# permamote.net
KiCad netlist of a schematic drawn in EAGLE
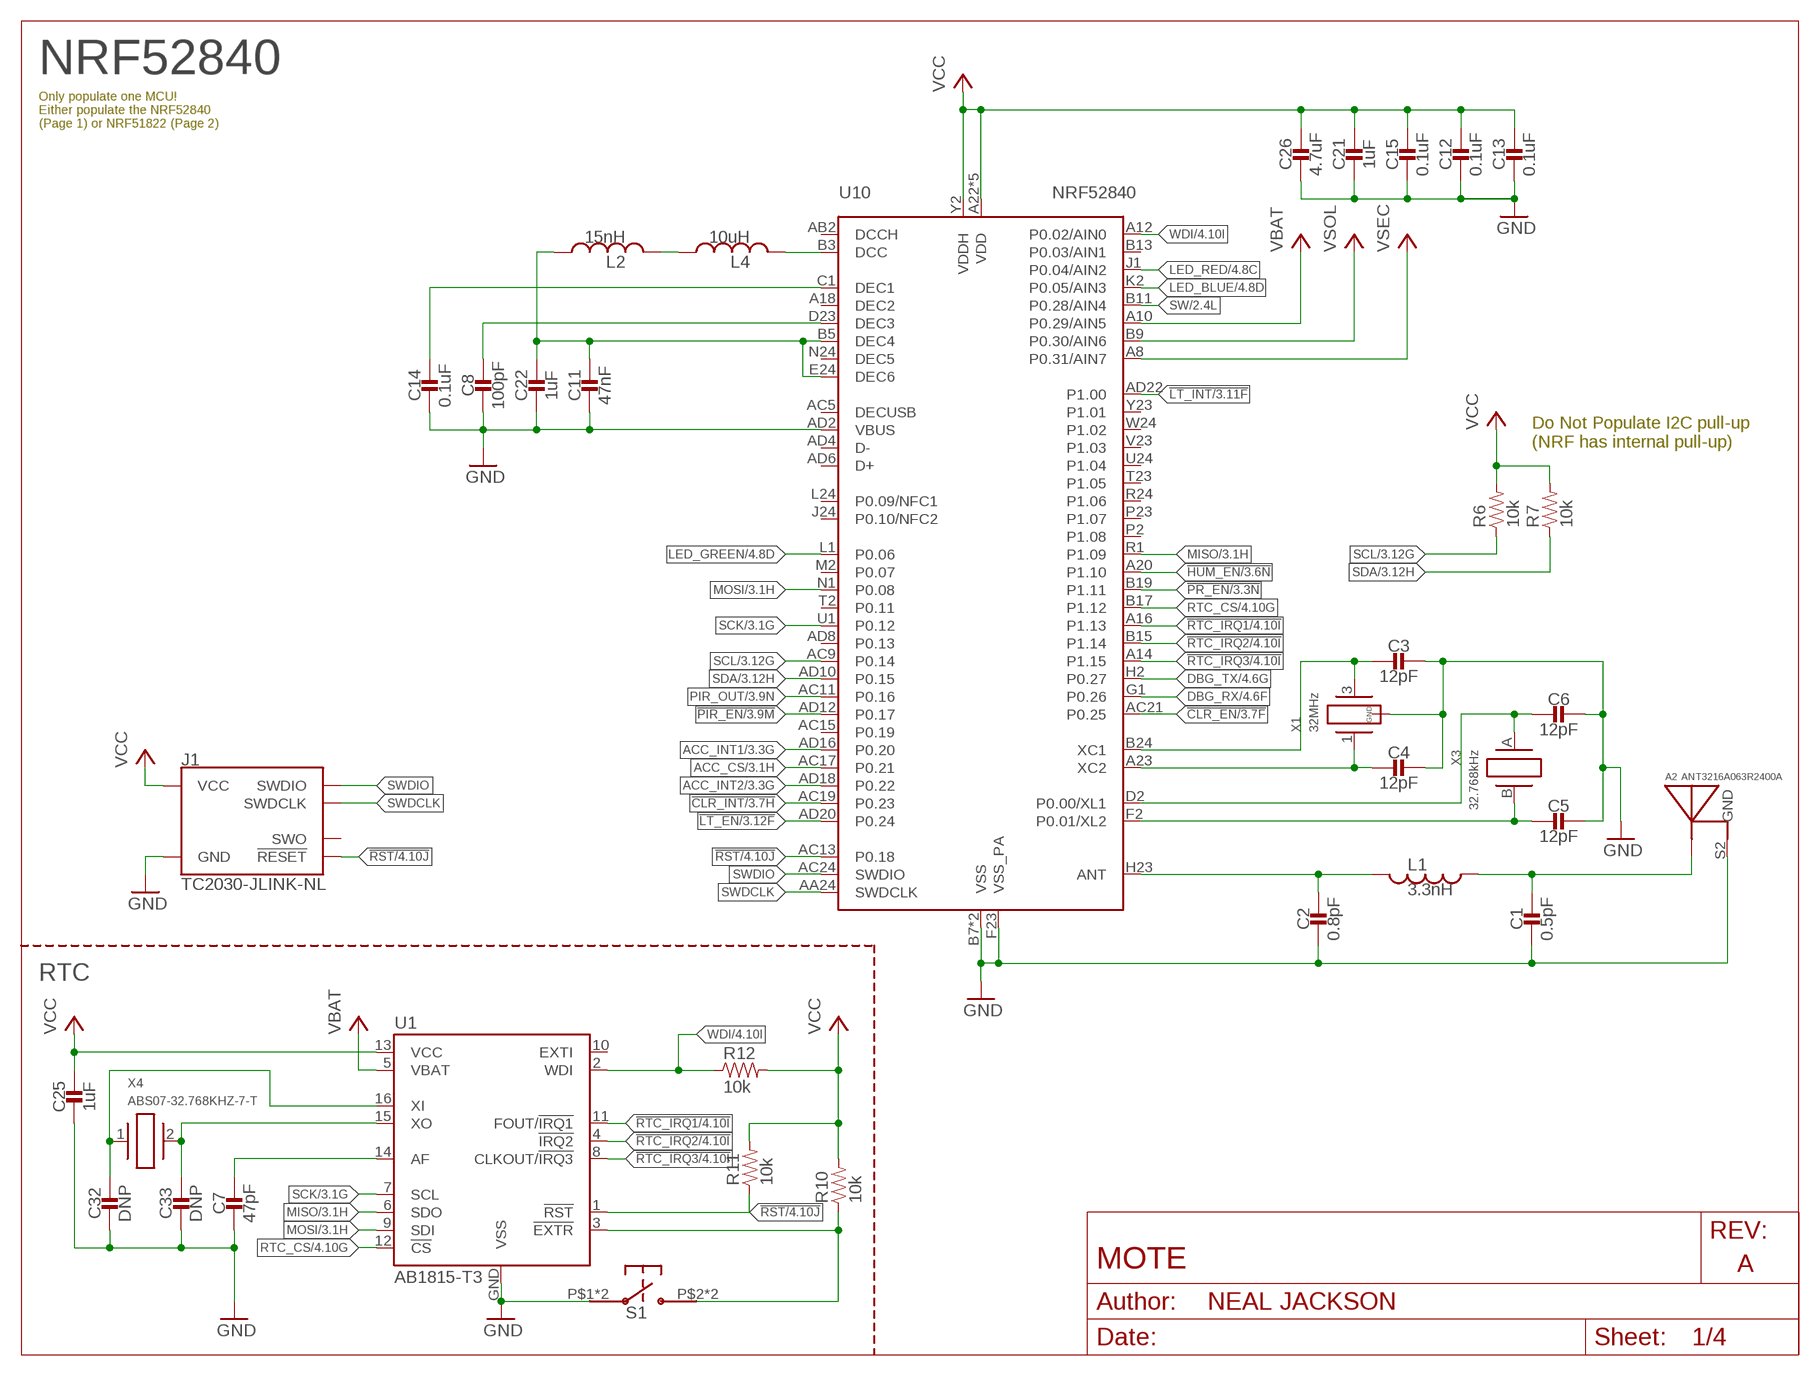
[diagram p0: schematic, sheet 1]
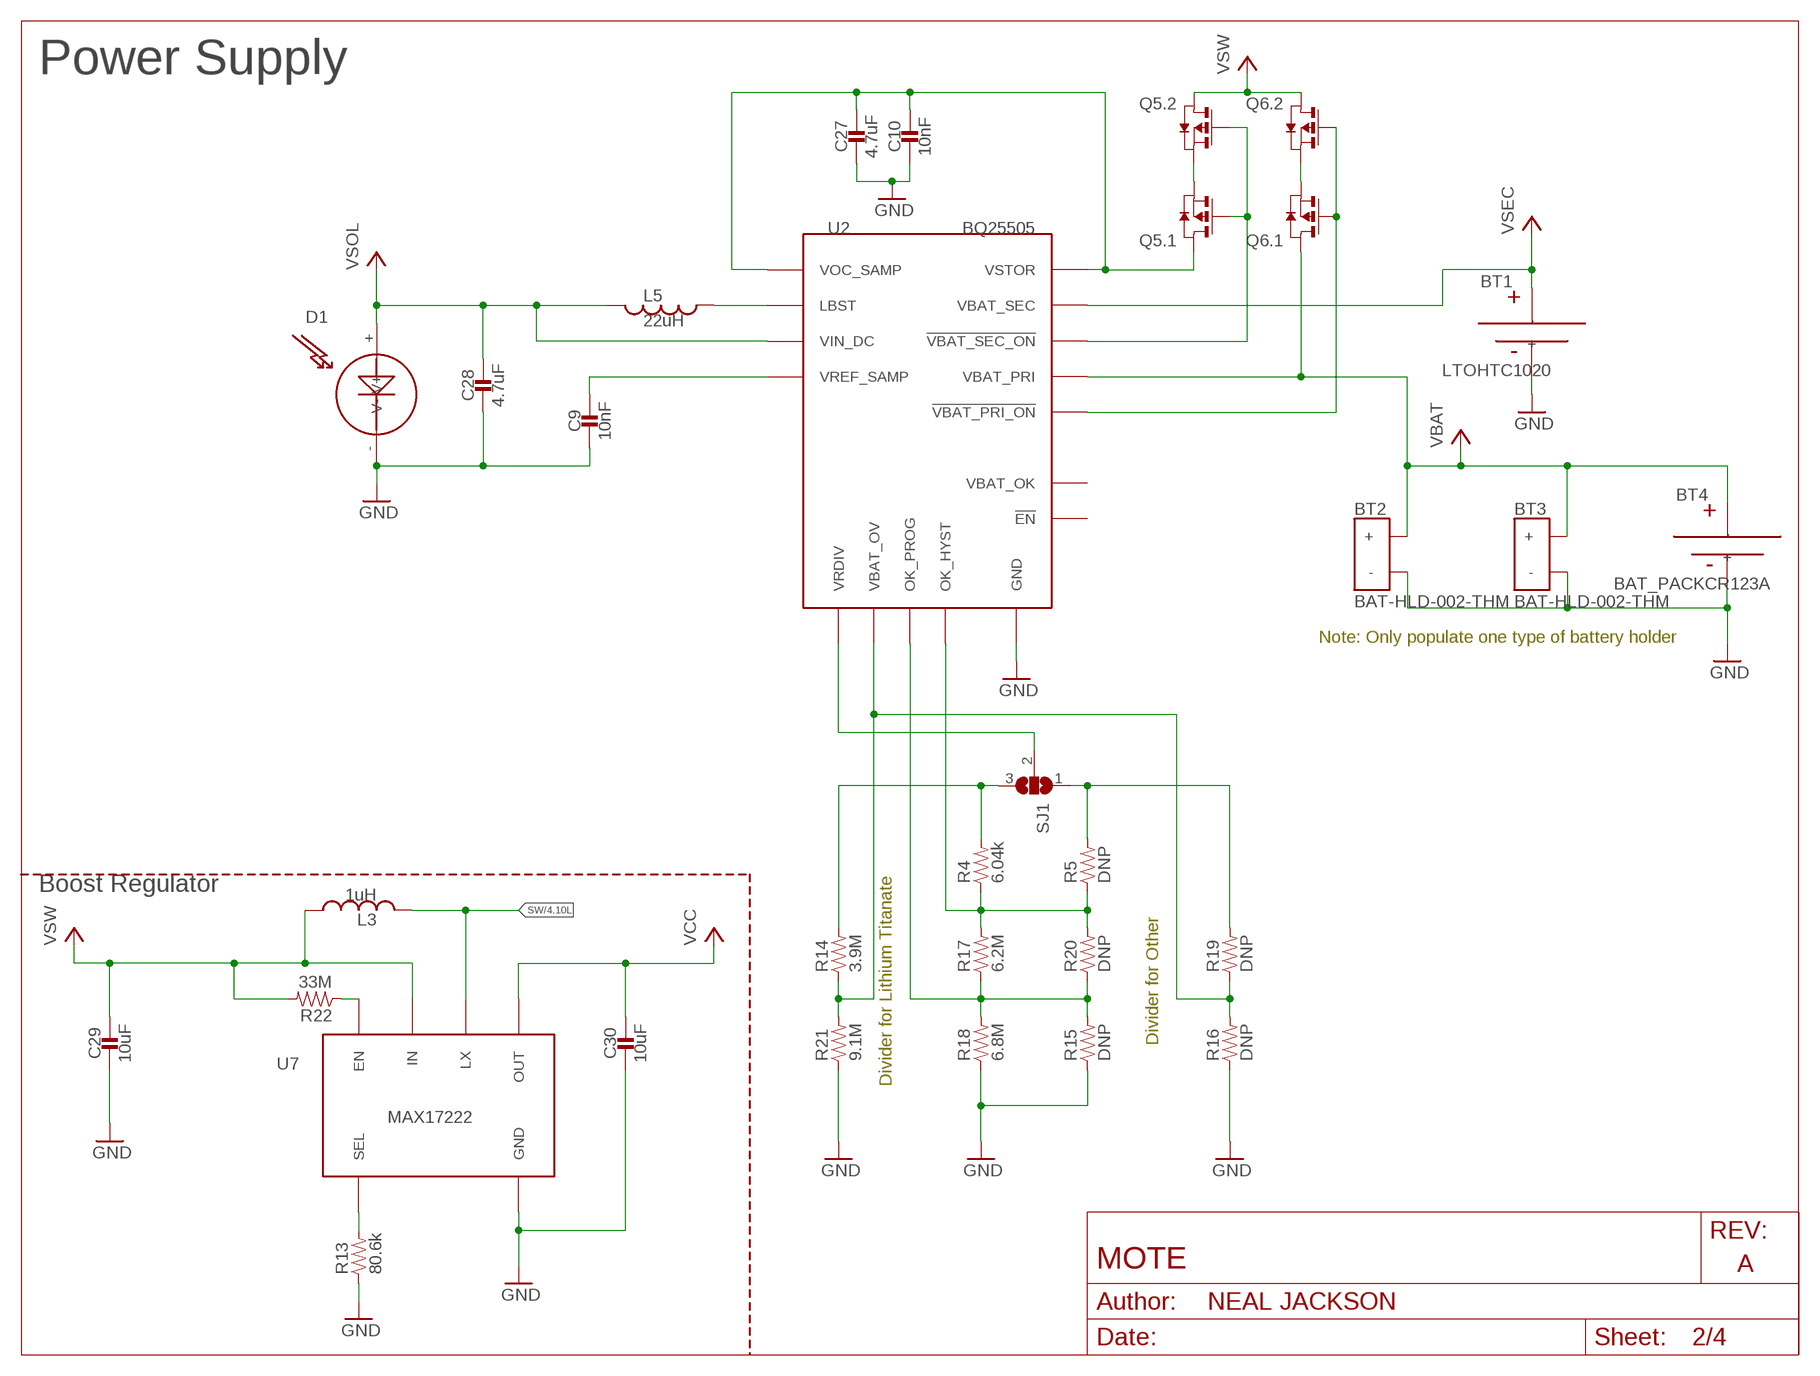
[diagram p1: schematic, sheet 2]
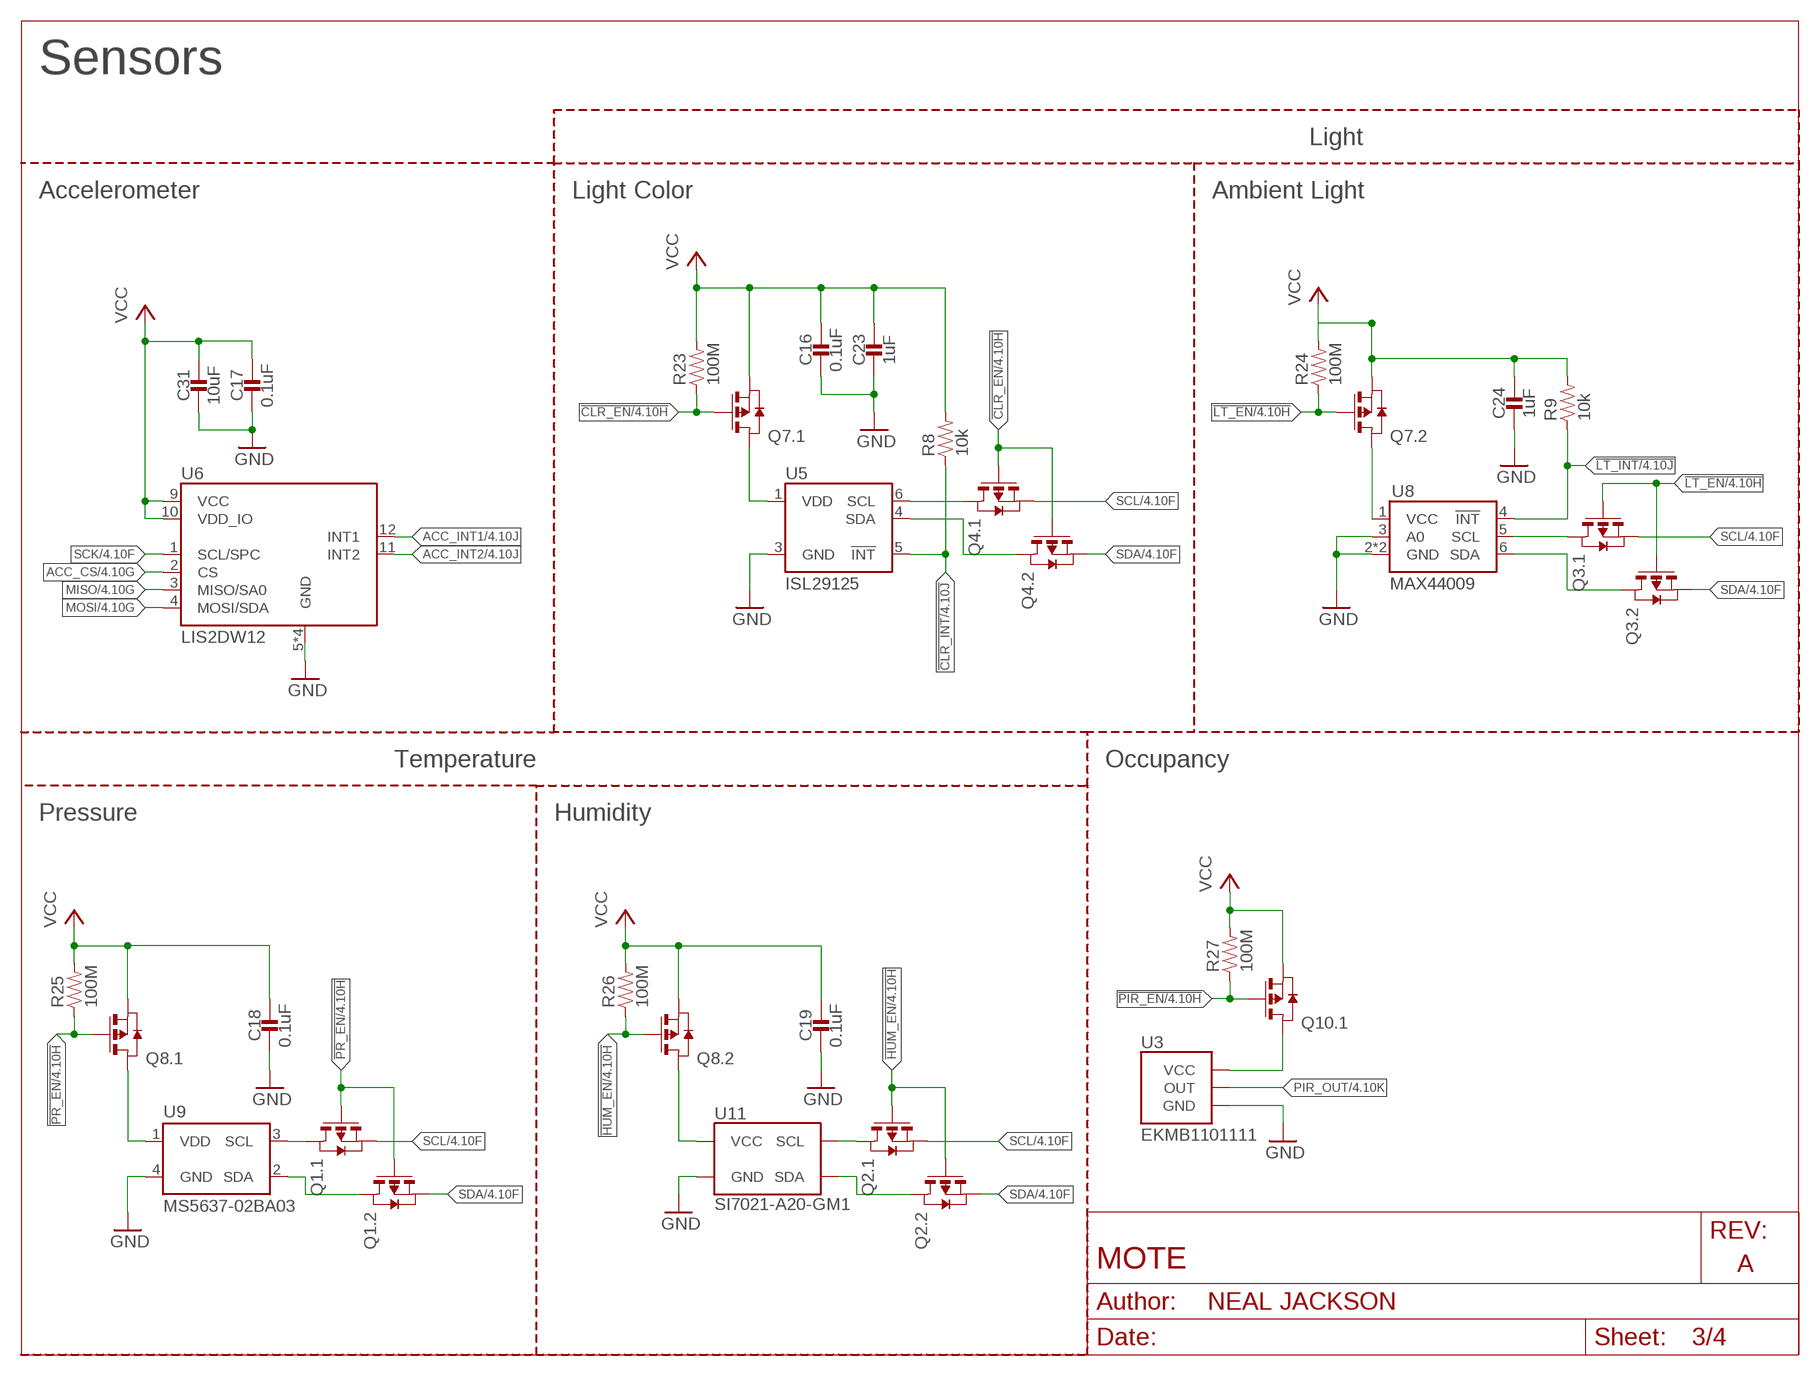
[diagram p2: schematic, sheet 3]
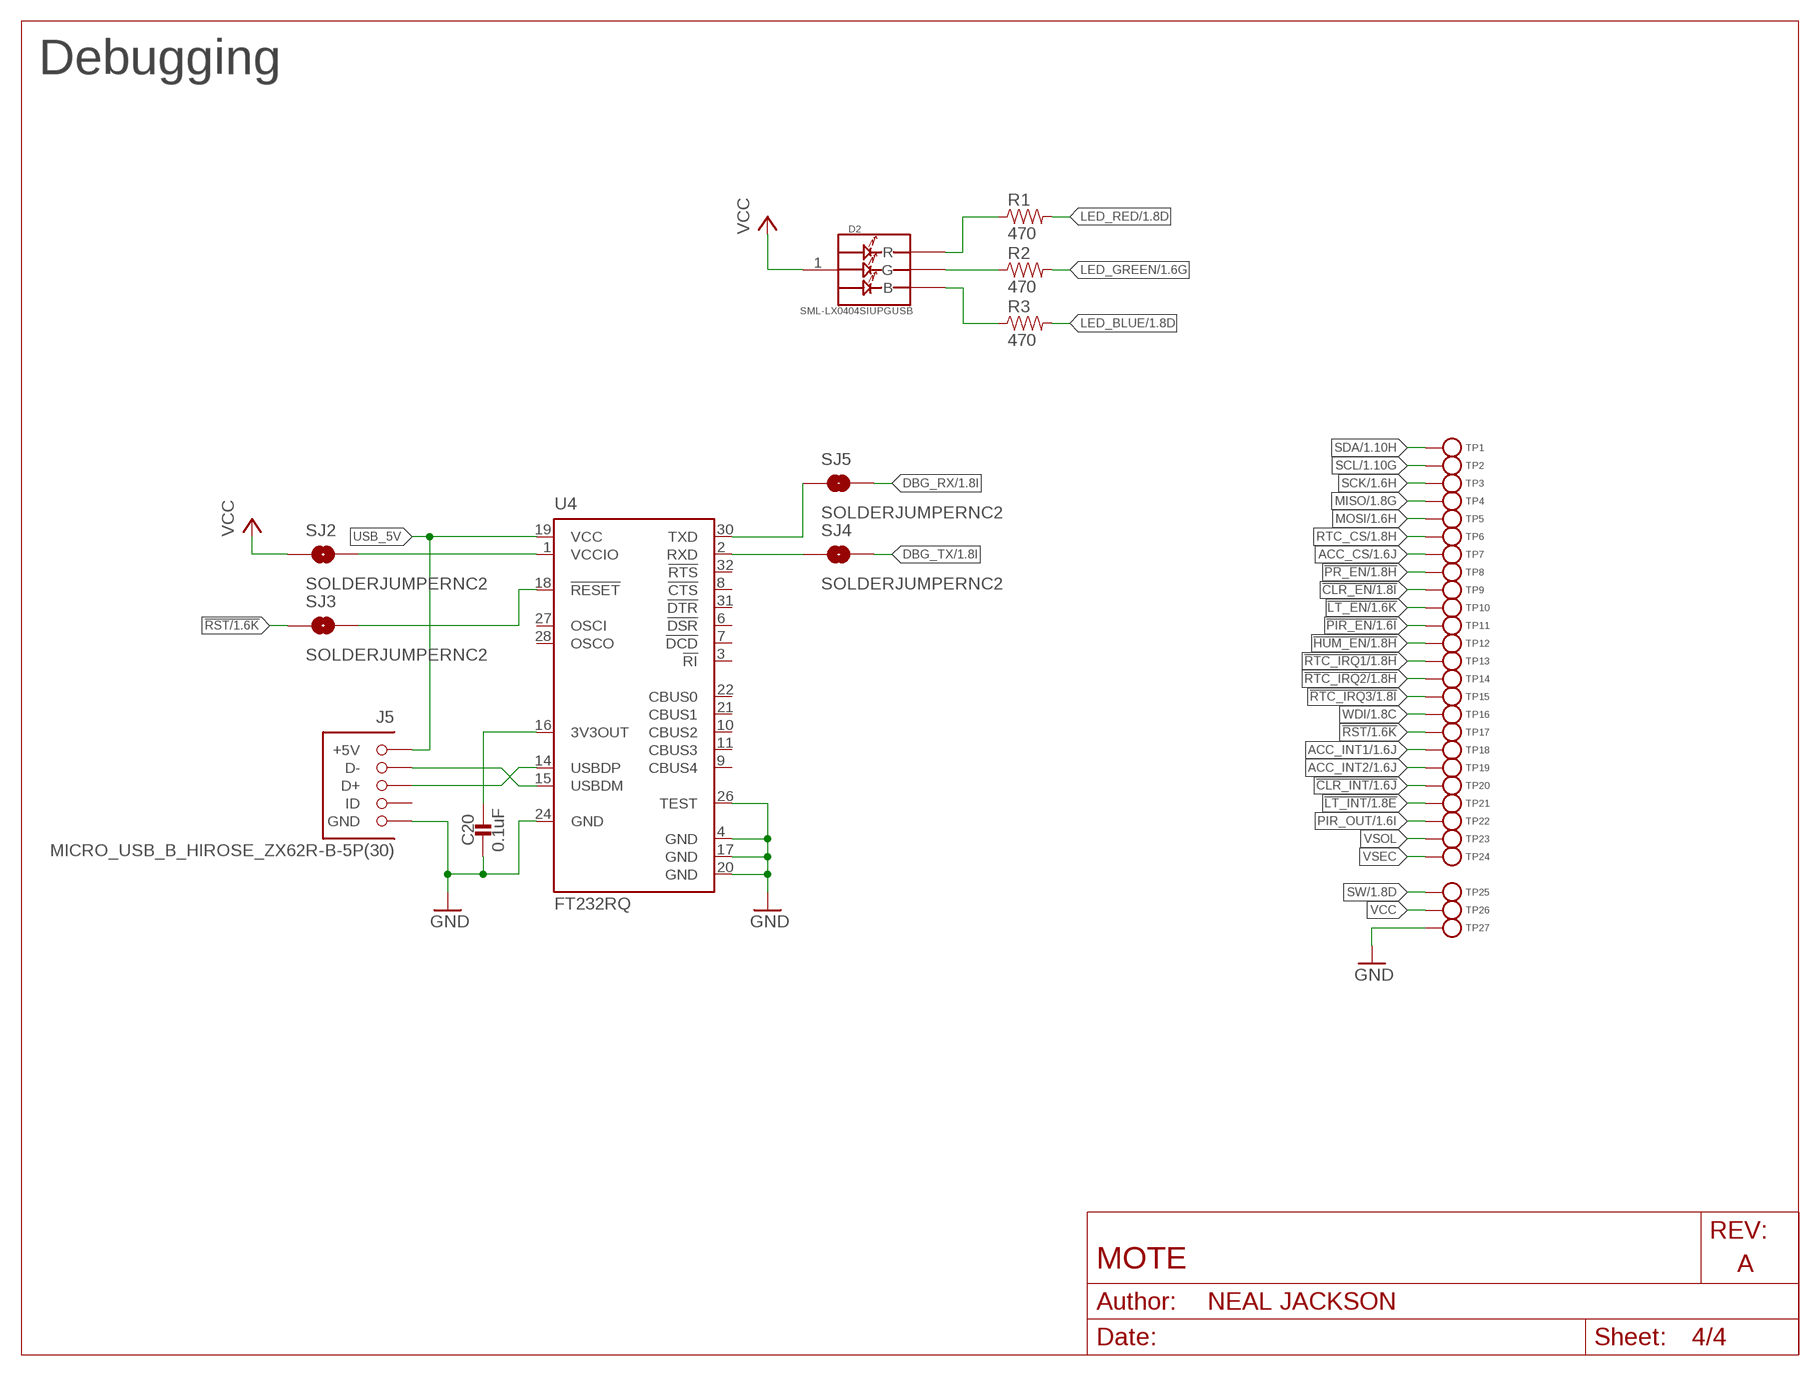
[diagram p3: schematic, sheet 4]

(export (version "E")
  (design (tool "Eeschema 10.0.6"))
  (components
    (comp (ref "C16")
      (value "0.1uF")
      (footprint "eagle-import:0402_CAP")
      (fields (field (name "MPN") "GRM155R71C104KA88J "))
      (libsource (lib "eagle-import") (part "CAPACITOR0402_CAP"))
    )
    (comp (ref "C17")
      (value "0.1uF")
      (footprint "eagle-import:0402_CAP")
      (fields (field (name "MPN") "GRM155R71C104KA88J "))
      (libsource (lib "eagle-import") (part "CAPACITOR0402_CAP"))
    )
    (comp (ref "C18")
      (value "0.1uF")
      (footprint "eagle-import:0402_CAP")
      (fields (field (name "MPN") "GRM155R71C104KA88J "))
      (libsource (lib "eagle-import") (part "CAPACITOR0402_CAP"))
    )
    (comp (ref "C19")
      (value "0.1uF")
      (footprint "eagle-import:0402_CAP")
      (fields (field (name "MPN") "GRM155R71C104KA88J "))
      (libsource (lib "eagle-import") (part "CAPACITOR0402_CAP"))
    )
    (comp (ref "C23")
      (value "1uF")
      (footprint "eagle-import:0402_CAP")
      (fields (field (name "MPN") "GRM155R70G105KA12D "))
      (libsource (lib "eagle-import") (part "CAPACITOR0402_CAP"))
    )
    (comp (ref "C24")
      (value "1uF")
      (footprint "eagle-import:0402_CAP")
      (fields (field (name "MPN") "GRM155R70G105KA12D "))
      (libsource (lib "eagle-import") (part "CAPACITOR0402_CAP"))
    )
    (comp (ref "C31")
      (value "10uF")
      (footprint "eagle-import:0603_CAP")
      (fields (field (name "MPN") "GRM188R60J106ME47D "))
      (libsource (lib "eagle-import") (part "CAPACITOR0603_CAP"))
    )
    (comp (ref "Q1")
      (value "PMDXB950UPEL")
      (footprint "eagle-import:XDFN-6")
      (fields (field (name "MANUFACTURER") "NEXPERIA") (field (name "MPN") "PMDXB950UPELZ"))
      (libsource (lib "eagle-import") (part "PMDXB950UPEL"))
    )
    (comp (ref "Q2")
      (value "PMDXB950UPEL")
      (footprint "eagle-import:XDFN-6")
      (fields (field (name "MANUFACTURER") "NEXPERIA") (field (name "MPN") "PMDXB950UPELZ"))
      (libsource (lib "eagle-import") (part "PMDXB950UPEL"))
    )
    (comp (ref "Q3")
      (value "PMDXB950UPEL")
      (footprint "eagle-import:XDFN-6")
      (fields (field (name "MANUFACTURER") "NEXPERIA") (field (name "MPN") "PMDXB950UPELZ"))
      (libsource (lib "eagle-import") (part "PMDXB950UPEL"))
    )
    (comp (ref "Q4")
      (value "PMDXB950UPEL")
      (footprint "eagle-import:XDFN-6")
      (fields (field (name "MANUFACTURER") "NEXPERIA") (field (name "MPN") "PMDXB950UPELZ"))
      (libsource (lib "eagle-import") (part "PMDXB950UPEL"))
    )
    (comp (ref "Q7")
      (value "PMDXB950UPEL")
      (footprint "eagle-import:XDFN-6")
      (fields (field (name "MANUFACTURER") "NEXPERIA") (field (name "MPN") "PMDXB950UPELZ"))
      (libsource (lib "eagle-import") (part "PMDXB950UPEL"))
    )
    (comp (ref "Q8")
      (value "PMDXB950UPEL")
      (footprint "eagle-import:XDFN-6")
      (fields (field (name "MANUFACTURER") "NEXPERIA") (field (name "MPN") "PMDXB950UPELZ"))
      (libsource (lib "eagle-import") (part "PMDXB950UPEL"))
    )
    (comp (ref "Q10")
      (value "PMDXB950UPEL")
      (footprint "eagle-import:XDFN-6")
      (fields (field (name "MANUFACTURER") "NEXPERIA") (field (name "MPN") "PMDXB950UPELZ"))
      (libsource (lib "eagle-import") (part "PMDXB950UPEL"))
    )
    (comp (ref "R8")
      (value "10k")
      (footprint "eagle-import:0402_RES")
      (fields (field (name "MPN") "RC0402JR-0710KL"))
      (libsource (lib "eagle-import") (part "RESISTOR0402_RES"))
    )
    (comp (ref "R9")
      (value "10k")
      (footprint "eagle-import:0402_RES")
      (fields (field (name "MPN") "RC0402JR-0710KL"))
      (libsource (lib "eagle-import") (part "RESISTOR0402_RES"))
    )
    (comp (ref "R23")
      (value "100M")
      (footprint "eagle-import:0402_RES")
      (fields (field (name "MPN") "HMC0402JT100M "))
      (libsource (lib "eagle-import") (part "RESISTOR0402_RES"))
    )
    (comp (ref "R24")
      (value "100M")
      (footprint "eagle-import:0402_RES")
      (fields (field (name "MPN") "HMC0402JT100M "))
      (libsource (lib "eagle-import") (part "RESISTOR0402_RES"))
    )
    (comp (ref "R25")
      (value "100M")
      (footprint "eagle-import:0402_RES")
      (fields (field (name "MPN") "HMC0402JT100M "))
      (libsource (lib "eagle-import") (part "RESISTOR0402_RES"))
    )
    (comp (ref "R26")
      (value "100M")
      (footprint "eagle-import:0402_RES")
      (fields (field (name "MPN") "HMC0402JT100M "))
      (libsource (lib "eagle-import") (part "RESISTOR0402_RES"))
    )
    (comp (ref "R27")
      (value "100M")
      (footprint "eagle-import:0402_RES")
      (fields (field (name "MPN") "HMC0402JT100M "))
      (libsource (lib "eagle-import") (part "RESISTOR0402_RES"))
    )
    (comp (ref "U3")
      (value "EKMB1101111")
      (footprint "eagle-import:AMN2")
      (fields (field (name "MANUFACTURER") "PANASONIC"))
      (libsource (lib "eagle-import") (part "EKMB1101111"))
    )
    (comp (ref "U5")
      (value "ISL29125")
      (footprint "eagle-import:ODFN-6-1.5MMX1.6MM")
      (fields (field (name "MANUFACTURER") "INTERSIL") (field (name "MPN") "ISL29125IROZ-T7A"))
      (libsource (lib "eagle-import") (part "ISL29125"))
    )
    (comp (ref "U6")
      (value "LIS2DW12")
      (footprint "eagle-import:LGA-12")
      (fields (field (name "MANUFACTURER") "STMicroelectronics") (field (name "MPN") "LIS2DW12TR"))
      (libsource (lib "eagle-import") (part "LIS2DW12"))
    )
    (comp (ref "U8")
      (value "MAX44009")
      (footprint "eagle-import:UDFN-6-EXPOSED")
      (fields (field (name "MANUFACTURER") "MAXIM") (field (name "MPN") "MAX44009EDT+T"))
      (libsource (lib "eagle-import") (part "MAX44009"))
    )
    (comp (ref "U9")
      (value "MS5637-02BA03")
      (footprint "eagle-import:4-SMD")
      (fields (field (name "MANUFACTURER") "TE CONNECTIVITY") (field (name "MPN") "MS563702BA03-50"))
      (libsource (lib "eagle-import") (part "MS5637-02BA03"))
    )
    (comp (ref "U11")
      (value "SI7021-A20-GM1")
      (footprint "eagle-import:DFN-6_3MM")
      (fields (field (name "MPN") "SI7021-A20-GM1 "))
      (libsource (lib "eagle-import") (part "SI7021-A20-GM1"))
    )
    (comp (ref "C20")
      (value "0.1uF")
      (footprint "eagle-import:0402_CAP")
      (fields (field (name "MPN") "GRM155R71C104KA88J "))
      (libsource (lib "eagle-import") (part "CAPACITOR0402_CAP"))
    )
    (comp (ref "D2")
      (value "SML-LX0404SIUPGUSB")
      (footprint "eagle-import:1MM_SQ_4PAD")
      (fields (field (name "MANUFACTURER") "Lumex Opto"))
      (libsource (lib "eagle-import") (part "SML-LX0404SIUPGUSB"))
    )
    (comp (ref "J5")
      (value "MICRO_USB_B_HIROSE_ZX62R-B-5P(30)")
      (footprint "eagle-import:MICRO_USB_B_HIROSE_ZX62R-B-5P(30)")
      (fields (field (name "MPN") "ZX62R-B-5P(30)"))
      (libsource (lib "eagle-import") (part "MICRO_USB_B_HIROSE_ZX62R-B-5P(30)"))
    )
    (comp (ref "R1")
      (value "470")
      (footprint "eagle-import:0402_RES")
      (fields (field (name "MPN") "RC0402JR-07470RL "))
      (libsource (lib "eagle-import") (part "RESISTOR0402_RES"))
    )
    (comp (ref "R2")
      (value "470")
      (footprint "eagle-import:0402_RES")
      (fields (field (name "MPN") "RC0402JR-07470RL "))
      (libsource (lib "eagle-import") (part "RESISTOR0402_RES"))
    )
    (comp (ref "R3")
      (value "470")
      (footprint "eagle-import:0402_RES")
      (fields (field (name "MPN") "RC0402JR-07470RL "))
      (libsource (lib "eagle-import") (part "RESISTOR0402_RES"))
    )
    (comp (ref "SJ2")
      (value "SOLDERJUMPERNC2")
      (footprint "eagle-import:SJ_2S-NOTRACE")
      (libsource (lib "eagle-import") (part "SOLDERJUMPERNC2"))
    )
    (comp (ref "SJ3")
      (value "SOLDERJUMPERNC2")
      (footprint "eagle-import:SJ_2S-NOTRACE")
      (libsource (lib "eagle-import") (part "SOLDERJUMPERNC2"))
    )
    (comp (ref "SJ4")
      (value "SOLDERJUMPERNC2")
      (footprint "eagle-import:SJ_2S-NOTRACE")
      (libsource (lib "eagle-import") (part "SOLDERJUMPERNC2"))
    )
    (comp (ref "SJ5")
      (value "SOLDERJUMPERNC2")
      (footprint "eagle-import:SJ_2S-NOTRACE")
      (libsource (lib "eagle-import") (part "SOLDERJUMPERNC2"))
    )
    (comp (ref "TP1")
      (value "TEST-POINT")
      (footprint "eagle-import:PAD.03X.03")
      (libsource (lib "eagle-import") (part "TEST-POINT"))
    )
    (comp (ref "TP2")
      (value "TEST-POINT")
      (footprint "eagle-import:PAD.03X.03")
      (libsource (lib "eagle-import") (part "TEST-POINT"))
    )
    (comp (ref "TP3")
      (value "TEST-POINT")
      (footprint "eagle-import:PAD.03X.03")
      (libsource (lib "eagle-import") (part "TEST-POINT"))
    )
    (comp (ref "TP4")
      (value "TEST-POINT")
      (footprint "eagle-import:PAD.03X.03")
      (libsource (lib "eagle-import") (part "TEST-POINT"))
    )
    (comp (ref "TP5")
      (value "TEST-POINT")
      (footprint "eagle-import:PAD.03X.03")
      (libsource (lib "eagle-import") (part "TEST-POINT"))
    )
    (comp (ref "TP6")
      (value "TEST-POINT")
      (footprint "eagle-import:PAD.03X.03")
      (libsource (lib "eagle-import") (part "TEST-POINT"))
    )
    (comp (ref "TP7")
      (value "TEST-POINT")
      (footprint "eagle-import:PAD.03X.03")
      (libsource (lib "eagle-import") (part "TEST-POINT"))
    )
    (comp (ref "TP8")
      (value "TEST-POINT")
      (footprint "eagle-import:PAD.03X.03")
      (libsource (lib "eagle-import") (part "TEST-POINT"))
    )
    (comp (ref "TP9")
      (value "TEST-POINT")
      (footprint "eagle-import:PAD.03X.03")
      (libsource (lib "eagle-import") (part "TEST-POINT"))
    )
    (comp (ref "TP10")
      (value "TEST-POINT")
      (footprint "eagle-import:PAD.03X.03")
      (libsource (lib "eagle-import") (part "TEST-POINT"))
    )
    (comp (ref "TP11")
      (value "TEST-POINT")
      (footprint "eagle-import:PAD.03X.03")
      (libsource (lib "eagle-import") (part "TEST-POINT"))
    )
    (comp (ref "TP12")
      (value "TEST-POINT")
      (footprint "eagle-import:PAD.03X.03")
      (libsource (lib "eagle-import") (part "TEST-POINT"))
    )
    (comp (ref "TP13")
      (value "TEST-POINT")
      (footprint "eagle-import:PAD.03X.03")
      (libsource (lib "eagle-import") (part "TEST-POINT"))
    )
    (comp (ref "TP14")
      (value "TEST-POINT")
      (footprint "eagle-import:PAD.03X.03")
      (libsource (lib "eagle-import") (part "TEST-POINT"))
    )
    (comp (ref "TP15")
      (value "TEST-POINT")
      (footprint "eagle-import:PAD.03X.03")
      (libsource (lib "eagle-import") (part "TEST-POINT"))
    )
    (comp (ref "TP16")
      (value "TEST-POINT")
      (footprint "eagle-import:PAD.03X.03")
      (libsource (lib "eagle-import") (part "TEST-POINT"))
    )
    (comp (ref "TP17")
      (value "TEST-POINT")
      (footprint "eagle-import:PAD.03X.03")
      (libsource (lib "eagle-import") (part "TEST-POINT"))
    )
    (comp (ref "TP18")
      (value "TEST-POINT")
      (footprint "eagle-import:PAD.03X.03")
      (libsource (lib "eagle-import") (part "TEST-POINT"))
    )
    (comp (ref "TP19")
      (value "TEST-POINT")
      (footprint "eagle-import:PAD.03X.03")
      (libsource (lib "eagle-import") (part "TEST-POINT"))
    )
    (comp (ref "TP20")
      (value "TEST-POINT")
      (footprint "eagle-import:PAD.03X.03")
      (libsource (lib "eagle-import") (part "TEST-POINT"))
    )
    (comp (ref "TP21")
      (value "TEST-POINT")
      (footprint "eagle-import:PAD.03X.03")
      (libsource (lib "eagle-import") (part "TEST-POINT"))
    )
    (comp (ref "TP22")
      (value "TEST-POINT")
      (footprint "eagle-import:PAD.03X.03")
      (libsource (lib "eagle-import") (part "TEST-POINT"))
    )
    (comp (ref "TP23")
      (value "TEST-POINT")
      (footprint "eagle-import:PAD.03X.03")
      (libsource (lib "eagle-import") (part "TEST-POINT"))
    )
    (comp (ref "TP24")
      (value "TEST-POINT")
      (footprint "eagle-import:PAD.03X.03")
      (libsource (lib "eagle-import") (part "TEST-POINT"))
    )
    (comp (ref "TP25")
      (value "TEST-POINT")
      (footprint "eagle-import:PAD.03X.03")
      (libsource (lib "eagle-import") (part "TEST-POINT"))
    )
    (comp (ref "TP26")
      (value "TEST-POINT")
      (footprint "eagle-import:PAD.03X.03")
      (libsource (lib "eagle-import") (part "TEST-POINT"))
    )
    (comp (ref "TP27")
      (value "TEST-POINT")
      (footprint "eagle-import:PAD.03X.03")
      (libsource (lib "eagle-import") (part "TEST-POINT"))
    )
    (comp (ref "U4")
      (value "FT232RQ")
      (footprint "eagle-import:QFN32")
      (libsource (lib "eagle-import") (part "FT232RQ"))
    )
    (comp (ref "BT1")
      (value "LTOHTC1020")
      (footprint "eagle-import:1020")
      (libsource (lib "eagle-import") (part "LTOHTC1020"))
    )
    (comp (ref "BT2")
      (value "BAT-HLD-002-THM")
      (footprint "eagle-import:BAT-HLD-002-THM")
      (fields
        (field (name "DIGIKEY") "BAT-HLD-001-THM-ND")
        (field (name "MOUSER") "712-BAT-HLD-001-THM")
        (field (name "MPN") "BAT-HLD-001-THM")
      )
      (libsource (lib "eagle-import") (part "BAT-HLD-002-THM"))
    )
    (comp (ref "BT3")
      (value "BAT-HLD-002-THM")
      (footprint "eagle-import:BAT-HLD-002-THM")
      (fields
        (field (name "DIGIKEY") "BAT-HLD-001-THM-ND")
        (field (name "MOUSER") "712-BAT-HLD-001-THM")
        (field (name "MPN") "BAT-HLD-001-THM")
      )
      (libsource (lib "eagle-import") (part "BAT-HLD-002-THM"))
    )
    (comp (ref "BT4")
      (value "BAT_PACKCR123A")
      (footprint "eagle-import:BH123A")
      (fields (field (name "MANUFACTURER") "MPD") (field (name "MPN") "BH123A"))
      (libsource (lib "eagle-import") (part "BAT_PACKCR123A"))
    )
    (comp (ref "C9")
      (value "10nF")
      (footprint "eagle-import:0402_CAP")
      (fields (field (name "MPN") "GRM155R71H103KA88D "))
      (libsource (lib "eagle-import") (part "CAPACITOR0402_CAP"))
    )
    (comp (ref "C10")
      (value "10nF")
      (footprint "eagle-import:0402_CAP")
      (fields (field (name "MPN") "GRM155R71H103KA88D "))
      (libsource (lib "eagle-import") (part "CAPACITOR0402_CAP"))
    )
    (comp (ref "C27")
      (value "4.7uF")
      (footprint "eagle-import:0402_CAP")
      (fields (field (name "MPN") "C1005X5R0J475K050BC "))
      (libsource (lib "eagle-import") (part "CAPACITOR0402_CAP"))
    )
    (comp (ref "C28")
      (value "4.7uF")
      (footprint "eagle-import:0402_CAP")
      (fields (field (name "MPN") "C1005X5R0J475K050BC "))
      (libsource (lib "eagle-import") (part "CAPACITOR0402_CAP"))
    )
    (comp (ref "C29")
      (value "10uF")
      (footprint "eagle-import:0603_CAP")
      (fields (field (name "MPN") "GRM188R60J106ME47D "))
      (libsource (lib "eagle-import") (part "CAPACITOR0603_CAP"))
    )
    (comp (ref "C30")
      (value "10uF")
      (footprint "eagle-import:0603_CAP")
      (fields (field (name "MPN") "GRM188R60J106ME47D "))
      (libsource (lib "eagle-import") (part "CAPACITOR0603_CAP"))
    )
    (comp (ref "D1")
      (value "SOLARCELLHOLES")
      (footprint "eagle-import:SOLAR_HOLES")
      (libsource (lib "eagle-import") (part "SOLARCELLHOLES"))
    )
    (comp (ref "L3")
      (value "1uH")
      (footprint "eagle-import:IHL-1212BZ-11")
      (fields
        (field (name "MANUFACTURER") "Vishay Dale")
        (field (name "MPN") "IHLP1212BZER2R2M11")
        (field (name "DIGIKEY") "541-1319-1-ND")
        (field (name "MPN_1") "IHLP1212BZER1R0M11")
      )
      (libsource (lib "eagle-import") (part "INDUCTORIHL"))
    )
    (comp (ref "L5")
      (value "22uH")
      (footprint "eagle-import:74437324220")
      (fields (field (name "DIGIKEY") "732-3340-1-ND") (field (name "MPN") "74437324220 "))
      (libsource (lib "eagle-import") (part "INDUCTOR74437324220"))
    )
    (comp (ref "Q5")
      (value "PMDXB950UPEL")
      (footprint "eagle-import:XDFN-6")
      (fields (field (name "MANUFACTURER") "NEXPERIA") (field (name "MPN") "PMDXB950UPELZ"))
      (libsource (lib "eagle-import") (part "PMDXB950UPEL"))
    )
    (comp (ref "Q6")
      (value "PMDXB950UPEL")
      (footprint "eagle-import:XDFN-6")
      (fields (field (name "MANUFACTURER") "NEXPERIA") (field (name "MPN") "PMDXB950UPELZ"))
      (libsource (lib "eagle-import") (part "PMDXB950UPEL"))
    )
    (comp (ref "R4")
      (value "6.04k")
      (footprint "eagle-import:0402_RES")
      (fields (field (name "MPN") "RC0402FR-076K04L"))
      (libsource (lib "eagle-import") (part "RESISTOR0402_RES"))
    )
    (comp (ref "R5")
      (value "DNP")
      (footprint "eagle-import:0402_RES")
      (libsource (lib "eagle-import") (part "RESISTOR0402_RES"))
    )
    (comp (ref "R13")
      (value "80.6k")
      (footprint "eagle-import:0603-RES")
      (fields (field (name "MPN") "RC0603FR-0780K6L "))
      (libsource (lib "eagle-import") (part "RESISTOR0603_RES"))
    )
    (comp (ref "R14")
      (value "3.9M")
      (footprint "eagle-import:0402_RES")
      (fields (field (name "MPN") "RC0402JR-073M9L"))
      (libsource (lib "eagle-import") (part "RESISTOR0402_RES"))
    )
    (comp (ref "R15")
      (value "DNP")
      (footprint "eagle-import:0402_RES")
      (libsource (lib "eagle-import") (part "RESISTOR0402_RES"))
    )
    (comp (ref "R16")
      (value "DNP")
      (footprint "eagle-import:0402_RES")
      (libsource (lib "eagle-import") (part "RESISTOR0402_RES"))
    )
    (comp (ref "R17")
      (value "6.2M")
      (footprint "eagle-import:0402_RES")
      (fields (field (name "MPN") "RC0402JR-076M2L"))
      (libsource (lib "eagle-import") (part "RESISTOR0402_RES"))
    )
    (comp (ref "R18")
      (value "6.8M")
      (footprint "eagle-import:0402_RES")
      (fields (field (name "MPN") "RC0402JR-076M8L"))
      (libsource (lib "eagle-import") (part "RESISTOR0402_RES"))
    )
    (comp (ref "R19")
      (value "DNP")
      (footprint "eagle-import:0402_RES")
      (libsource (lib "eagle-import") (part "RESISTOR0402_RES"))
    )
    (comp (ref "R20")
      (value "DNP")
      (footprint "eagle-import:0402_RES")
      (libsource (lib "eagle-import") (part "RESISTOR0402_RES"))
    )
    (comp (ref "R21")
      (value "9.1M")
      (footprint "eagle-import:0402_RES")
      (fields (field (name "MPN") "RC0402JR-079M1L"))
      (libsource (lib "eagle-import") (part "RESISTOR0402_RES"))
    )
    (comp (ref "R22")
      (value "33M")
      (footprint "eagle-import:0603-RES")
      (fields (field (name "MPN") "HMC0603JT33M0 "))
      (libsource (lib "eagle-import") (part "RESISTOR0603_RES"))
    )
    (comp (ref "SJ1")
      (value "SJ2W")
      (footprint "eagle-import:SJ_2")
      (libsource (lib "eagle-import") (part "SJ2W"))
    )
    (comp (ref "U2")
      (value "BQ25505")
      (footprint "eagle-import:S-PVQFN-N20-RGR")
      (fields (field (name "MANUFACTURER") "TI") (field (name "MPN") "BQ25505RGRR"))
      (libsource (lib "eagle-import") (part "BQ25505"))
    )
    (comp (ref "U7")
      (value "MAX17222")
      (footprint "eagle-import:UDFN-6-MAXIM")
      (fields (field (name "MANUFACTURER") "MAXIM INTEGRATED") (field (name "MPN") "MAX17222ELT+T"))
      (libsource (lib "eagle-import") (part "MAX17222"))
    )
    (comp (ref "A2")
      (value "ANT3216A063R2400A")
      (footprint "eagle-import:ANT3216A063R2400A")
      (fields (field (name "MANUFACTURER") "YAGEO"))
      (libsource (lib "eagle-import") (part "ANT3216A063R2400A"))
    )
    (comp (ref "C1")
      (value "0.5pF")
      (footprint "eagle-import:0402_CAP")
      (fields (field (name "MPN") "GRM1555C1HR50WA01D "))
      (libsource (lib "eagle-import") (part "CAPACITOR0402_CAP"))
    )
    (comp (ref "C2")
      (value "0.8pF")
      (footprint "eagle-import:0402_CAP")
      (fields (field (name "MPN") "GRM1555C1HR80BA01D "))
      (libsource (lib "eagle-import") (part "CAPACITOR0402_CAP"))
    )
    (comp (ref "C3")
      (value "12pF")
      (footprint "eagle-import:0402_CAP")
      (fields (field (name "MPN") "GRM1555C1H120GA01D "))
      (libsource (lib "eagle-import") (part "CAPACITOR0402_CAP"))
    )
    (comp (ref "C4")
      (value "12pF")
      (footprint "eagle-import:0402_CAP")
      (fields (field (name "MPN") "GRM1555C1H120GA01D "))
      (libsource (lib "eagle-import") (part "CAPACITOR0402_CAP"))
    )
    (comp (ref "C5")
      (value "12pF")
      (footprint "eagle-import:0402_CAP")
      (fields (field (name "MPN") "GRM1555C1H120GA01D "))
      (libsource (lib "eagle-import") (part "CAPACITOR0402_CAP"))
    )
    (comp (ref "C6")
      (value "12pF")
      (footprint "eagle-import:0402_CAP")
      (fields (field (name "MPN") "GRM1555C1H120GA01D "))
      (libsource (lib "eagle-import") (part "CAPACITOR0402_CAP"))
    )
    (comp (ref "C7")
      (value "47pF")
      (footprint "eagle-import:0402_CAP")
      (fields (field (name "MPN") "GRM1555C1H470JA01D "))
      (libsource (lib "eagle-import") (part "CAPACITOR0402_CAP"))
    )
    (comp (ref "C8")
      (value "100pF")
      (footprint "eagle-import:0402_CAP")
      (fields (field (name "MPN") "GRM1555C1H101JA01D "))
      (libsource (lib "eagle-import") (part "CAPACITOR0402_CAP"))
    )
    (comp (ref "C11")
      (value "47nF")
      (footprint "eagle-import:0402_CAP")
      (fields (field (name "MPN") "C1005X7R1C473K050BC "))
      (libsource (lib "eagle-import") (part "CAPACITOR0402_CAP"))
    )
    (comp (ref "C12")
      (value "0.1uF")
      (footprint "eagle-import:0402_CAP")
      (fields (field (name "MPN") "GRM155R71C104KA88J "))
      (libsource (lib "eagle-import") (part "CAPACITOR0402_CAP"))
    )
    (comp (ref "C13")
      (value "0.1uF")
      (footprint "eagle-import:0402_CAP")
      (fields (field (name "MPN") "GRM155R71C104KA88J "))
      (libsource (lib "eagle-import") (part "CAPACITOR0402_CAP"))
    )
    (comp (ref "C14")
      (value "0.1uF")
      (footprint "eagle-import:0402_CAP")
      (fields (field (name "MPN") "GRM155R71C104KA88J "))
      (libsource (lib "eagle-import") (part "CAPACITOR0402_CAP"))
    )
    (comp (ref "C15")
      (value "0.1uF")
      (footprint "eagle-import:0402_CAP")
      (fields (field (name "MPN") "GRM155R71C104KA88J "))
      (libsource (lib "eagle-import") (part "CAPACITOR0402_CAP"))
    )
    (comp (ref "C21")
      (value "1uF")
      (footprint "eagle-import:0402_CAP")
      (fields (field (name "MPN") "GRM155R70G105KA12D "))
      (libsource (lib "eagle-import") (part "CAPACITOR0402_CAP"))
    )
    (comp (ref "C22")
      (value "1uF")
      (footprint "eagle-import:0402_CAP")
      (fields (field (name "MPN") "GRM155R70G105KA12D "))
      (libsource (lib "eagle-import") (part "CAPACITOR0402_CAP"))
    )
    (comp (ref "C25")
      (value "1uF")
      (footprint "eagle-import:0402_CAP")
      (fields (field (name "MPN") "GRM155R70G105KA12D "))
      (libsource (lib "eagle-import") (part "CAPACITOR0402_CAP"))
    )
    (comp (ref "C26")
      (value "4.7uF")
      (footprint "eagle-import:0402_CAP")
      (fields (field (name "MPN") "C1005X5R0J475K050BC "))
      (libsource (lib "eagle-import") (part "CAPACITOR0402_CAP"))
    )
    (comp (ref "C32")
      (value "DNP")
      (footprint "eagle-import:0402_CAP")
      (libsource (lib "eagle-import") (part "CAPACITOR0402_CAP"))
    )
    (comp (ref "C33")
      (value "DNP")
      (footprint "eagle-import:0402_CAP")
      (libsource (lib "eagle-import") (part "CAPACITOR0402_CAP"))
    )
    (comp (ref "J1")
      (value "TC2030-JLINK-NL")
      (footprint "eagle-import:TC2030-IDC-NL")
      (libsource (lib "eagle-import") (part "TC2030-JLINK-NL"))
    )
    (comp (ref "L1")
      (value "3.3nH")
      (footprint "eagle-import:0402_CAP")
      (fields (field (name "MPN") "AISC-0402-3N3J-T "))
      (libsource (lib "eagle-import") (part "INDUCTOR0402"))
    )
    (comp (ref "L2")
      (value "15nH")
      (footprint "eagle-import:0402_CAP")
      (fields (field (name "MPN") "HK100515NJ-T "))
      (libsource (lib "eagle-import") (part "INDUCTOR0402"))
    )
    (comp (ref "L4")
      (value "10uH")
      (footprint "eagle-import:0603_CAP")
      (fields (field (name "MPN") "LQM18FN100M00D "))
      (libsource (lib "eagle-import") (part "INDUCTOR0603"))
    )
    (comp (ref "R6")
      (value "10k")
      (footprint "eagle-import:0402_RES")
      (fields (field (name "MPN") "RC0402JR-0710KL"))
      (libsource (lib "eagle-import") (part "RESISTOR0402_RES"))
    )
    (comp (ref "R7")
      (value "10k")
      (footprint "eagle-import:0402_RES")
      (fields (field (name "MPN") "RC0402JR-0710KL"))
      (libsource (lib "eagle-import") (part "RESISTOR0402_RES"))
    )
    (comp (ref "R10")
      (value "10k")
      (footprint "eagle-import:0402_RES")
      (fields (field (name "MPN") "RC0402JR-0710KL"))
      (libsource (lib "eagle-import") (part "RESISTOR0402_RES"))
    )
    (comp (ref "R11")
      (value "10k")
      (footprint "eagle-import:0402_RES")
      (fields (field (name "MPN") "RC0402JR-0710KL"))
      (libsource (lib "eagle-import") (part "RESISTOR0402_RES"))
    )
    (comp (ref "R12")
      (value "10k")
      (footprint "eagle-import:0402_RES")
      (fields (field (name "MPN") "RC0402JR-0710KL"))
      (libsource (lib "eagle-import") (part "RESISTOR0402_RES"))
    )
    (comp (ref "S1")
      (value "EVQP2")
      (footprint "eagle-import:EVQP2")
      (fields (field (name "MPN") "EVQ-P2K02Q "))
      (libsource (lib "eagle-import") (part "EVQP2"))
    )
    (comp (ref "U1")
      (value "AB1815-T3")
      (footprint "eagle-import:QFN-16-3MM")
      (fields (field (name "MANUFACTURER") "Abracon"))
      (libsource (lib "eagle-import") (part "AB1815-T3"))
    )
    (comp (ref "U10")
      (value "NRF52840")
      (footprint "eagle-import:AQFN73")
      (fields (field (name "MANUFACTURER") "NORIDIC SEMICONDUCTOR"))
      (libsource (lib "eagle-import") (part "NRF52840"))
    )
    (comp (ref "X1")
      (value "32MHz")
      (footprint "eagle-import:TXC-7V")
      (fields (field (name "MANUFACTURER") "TXC CORPORATION") (field (name "MPN") "7M-32.000MAHV-T"))
      (libsource (lib "eagle-import") (part "7V-32.000MAHV-T"))
    )
    (comp (ref "X3")
      (value "32.768kHz")
      (footprint "eagle-import:ABS05")
      (fields (field (name "MANUFACTURER") "Abracon") (field (name "MPN") "ABS05-32.768KHZ-9-T"))
      (libsource (lib "eagle-import") (part "ABS05-32.768KHZ-9-T"))
    )
    (comp (ref "X4")
      (value "ABS07-32.768KHZ-7-T")
      (footprint "eagle-import:2-SMD")
      (fields (field (name "MANUFACTURER") "ABRACON") (field (name "MPN") "ABS07-32.768KHZ-7-T "))
      (libsource (lib "eagle-import") (part "ABS07-32.768KHZ-7-T"))
    )
  )
  (nets
    (net (code "1") (name "ACC_CS") (class "Default")
      (node (ref "TP7") (pin "P$1") (pinfunction "TESTPOINT_P$1") (pintype "bidirectional"))
      (node (ref "U10") (pin "AC17") (pinfunction "P0.21_AC17") (pintype "bidirectional"))
      (node (ref "U6") (pin "2") (pinfunction "CS_2") (pintype "bidirectional"))
    )
    (net (code "2") (name "ACC_INT1") (class "Default")
      (node (ref "TP18") (pin "P$1") (pinfunction "TESTPOINT_P$1") (pintype "bidirectional"))
      (node (ref "U10") (pin "AD16") (pinfunction "P0.20_AD16") (pintype "bidirectional"))
      (node (ref "U6") (pin "12") (pinfunction "INT1_12") (pintype "bidirectional"))
    )
    (net (code "3") (name "ACC_INT2") (class "Default")
      (node (ref "TP19") (pin "P$1") (pinfunction "TESTPOINT_P$1") (pintype "bidirectional"))
      (node (ref "U10") (pin "AD18") (pinfunction "P0.22_AD18") (pintype "bidirectional"))
      (node (ref "U6") (pin "11") (pinfunction "INT2_11") (pintype "bidirectional"))
    )
    (net (code "4") (name "DBG_RX") (class "Default")
      (node (ref "SJ5") (pin "2") (pinfunction "2_2") (pintype "passive"))
      (node (ref "U10") (pin "G1") (pinfunction "P0.26_G1") (pintype "bidirectional"))
    )
    (net (code "5") (name "DBG_TX") (class "Default")
      (node (ref "SJ4") (pin "2") (pinfunction "2_2") (pintype "passive"))
      (node (ref "U10") (pin "H2") (pinfunction "P0.27_H2") (pintype "bidirectional"))
    )
    (net (code "6") (name "GND") (class "Default")
      (node (ref "A2") (pin "S2") (pinfunction "GND_S2") (pintype "bidirectional"))
      (node (ref "BT1") (pin "-") (pinfunction "-_-") (pintype "bidirectional"))
      (node (ref "BT2") (pin "GND") (pinfunction "-_GND") (pintype "bidirectional"))
      (node (ref "BT3") (pin "GND") (pinfunction "-_GND") (pintype "bidirectional"))
      (node (ref "BT4") (pin "-") (pinfunction "-_-") (pintype "bidirectional"))
      (node (ref "C1") (pin "2") (pinfunction "2_2") (pintype "bidirectional"))
      (node (ref "C10") (pin "2") (pinfunction "2_2") (pintype "bidirectional"))
      (node (ref "C11") (pin "2") (pinfunction "2_2") (pintype "bidirectional"))
      (node (ref "C12") (pin "2") (pinfunction "2_2") (pintype "bidirectional"))
      (node (ref "C13") (pin "2") (pinfunction "2_2") (pintype "bidirectional"))
      (node (ref "C14") (pin "2") (pinfunction "2_2") (pintype "bidirectional"))
      (node (ref "C15") (pin "2") (pinfunction "2_2") (pintype "bidirectional"))
      (node (ref "C16") (pin "2") (pinfunction "2_2") (pintype "bidirectional"))
      (node (ref "C17") (pin "2") (pinfunction "2_2") (pintype "bidirectional"))
      (node (ref "C18") (pin "2") (pinfunction "2_2") (pintype "bidirectional"))
      (node (ref "C19") (pin "2") (pinfunction "2_2") (pintype "bidirectional"))
      (node (ref "C2") (pin "2") (pinfunction "2_2") (pintype "bidirectional"))
      (node (ref "C20") (pin "2") (pinfunction "2_2") (pintype "bidirectional"))
      (node (ref "C21") (pin "2") (pinfunction "2_2") (pintype "bidirectional"))
      (node (ref "C22") (pin "2") (pinfunction "2_2") (pintype "bidirectional"))
      (node (ref "C23") (pin "2") (pinfunction "2_2") (pintype "bidirectional"))
      (node (ref "C24") (pin "2") (pinfunction "2_2") (pintype "bidirectional"))
      (node (ref "C25") (pin "2") (pinfunction "2_2") (pintype "bidirectional"))
      (node (ref "C26") (pin "2") (pinfunction "2_2") (pintype "bidirectional"))
      (node (ref "C27") (pin "2") (pinfunction "2_2") (pintype "bidirectional"))
      (node (ref "C28") (pin "2") (pinfunction "2_2") (pintype "bidirectional"))
      (node (ref "C29") (pin "2") (pinfunction "2_2") (pintype "bidirectional"))
      (node (ref "C3") (pin "1") (pinfunction "1_1") (pintype "bidirectional"))
      (node (ref "C30") (pin "2") (pinfunction "2_2") (pintype "bidirectional"))
      (node (ref "C31") (pin "2") (pinfunction "2_2") (pintype "bidirectional"))
      (node (ref "C32") (pin "2") (pinfunction "2_2") (pintype "bidirectional"))
      (node (ref "C33") (pin "2") (pinfunction "2_2") (pintype "bidirectional"))
      (node (ref "C4") (pin "1") (pinfunction "1_1") (pintype "bidirectional"))
      (node (ref "C5") (pin "1") (pinfunction "1_1") (pintype "bidirectional"))
      (node (ref "C6") (pin "1") (pinfunction "1_1") (pintype "bidirectional"))
      (node (ref "C7") (pin "2") (pinfunction "2_2") (pintype "bidirectional"))
      (node (ref "C8") (pin "2") (pinfunction "2_2") (pintype "bidirectional"))
      (node (ref "C9") (pin "2") (pinfunction "2_2") (pintype "bidirectional"))
      (node (ref "D1") (pin "-") (pinfunction "V-_-") (pintype "bidirectional"))
      (node (ref "J1") (pin "5") (pinfunction "GND_5") (pintype "bidirectional"))
      (node (ref "J5") (pin "5") (pinfunction "GND_5") (pintype "bidirectional"))
      (node (ref "R13") (pin "1") (pinfunction "1_1") (pintype "passive"))
      (node (ref "R15") (pin "1") (pinfunction "1_1") (pintype "passive"))
      (node (ref "R16") (pin "1") (pinfunction "1_1") (pintype "passive"))
      (node (ref "R18") (pin "1") (pinfunction "1_1") (pintype "passive"))
      (node (ref "R21") (pin "1") (pinfunction "1_1") (pintype "passive"))
      (node (ref "S1") (pin "P$1") (pinfunction "P$1_P$1") (pintype "passive"))
      (node (ref "S1") (pin "P$3") (pinfunction "P$1_P$3") (pintype "passive"))
      (node (ref "TP27") (pin "P$1") (pinfunction "TESTPOINT_P$1") (pintype "bidirectional"))
      (node (ref "U1") (pin "GND") (pinfunction "VSS_GND") (pintype "bidirectional"))
      (node (ref "U10") (pin "AD2") (pinfunction "VBUS_AD2") (pintype "bidirectional"))
      (node (ref "U10") (pin "B7") (pinfunction "VSS_B7") (pintype "bidirectional"))
      (node (ref "U10") (pin "F23") (pinfunction "VSS_PA_F23") (pintype "bidirectional"))
      (node (ref "U10") (pin "GND") (pinfunction "VSS_GND") (pintype "bidirectional"))
      (node (ref "U11") (pin "2") (pinfunction "GND_2") (pintype "bidirectional"))
      (node (ref "U2") (pin "1") (pinfunction "GND_1") (pintype "bidirectional"))
      (node (ref "U2") (pin "15") (pinfunction "GND_15") (pintype "bidirectional"))
      (node (ref "U2") (pin "16") (pinfunction "GND_16") (pintype "bidirectional"))
      (node (ref "U2") (pin "17") (pinfunction "GND_17") (pintype "bidirectional"))
      (node (ref "U2") (pin "6") (pinfunction "GND_6") (pintype "bidirectional"))
      (node (ref "U2") (pin "PAD") (pinfunction "GND_PAD") (pintype "bidirectional"))
      (node (ref "U3") (pin "GND") (pinfunction "GND_GND") (pintype "bidirectional"))
      (node (ref "U4") (pin "17") (pinfunction "GND_17") (pintype "power_in"))
      (node (ref "U4") (pin "20") (pinfunction "GND_20") (pintype "power_in"))
      (node (ref "U4") (pin "24") (pinfunction "GND_24") (pintype "power_in"))
      (node (ref "U4") (pin "26") (pinfunction "TEST_26") (pintype "input"))
      (node (ref "U4") (pin "4") (pinfunction "GND_4") (pintype "power_in"))
      (node (ref "U5") (pin "3") (pinfunction "GND_3") (pintype "bidirectional"))
      (node (ref "U6") (pin "5") (pinfunction "GND_5") (pintype "bidirectional"))
      (node (ref "U6") (pin "6") (pinfunction "GND_6") (pintype "bidirectional"))
      (node (ref "U6") (pin "7") (pinfunction "GND_7") (pintype "bidirectional"))
      (node (ref "U6") (pin "8") (pinfunction "GND_8") (pintype "bidirectional"))
      (node (ref "U7") (pin "3") (pinfunction "GND_3") (pintype "bidirectional"))
      (node (ref "U8") (pin "2") (pinfunction "GND_2") (pintype "bidirectional"))
      (node (ref "U8") (pin "3") (pinfunction "A0_3") (pintype "bidirectional"))
      (node (ref "U8") (pin "EP") (pinfunction "GND_EP") (pintype "bidirectional"))
      (node (ref "U9") (pin "4") (pinfunction "GND_4") (pintype "bidirectional"))
      (node (ref "X1") (pin "2") (pinfunction "GND_2") (pintype "bidirectional"))
      (node (ref "X1") (pin "4") (pinfunction "GND_4") (pintype "bidirectional"))
    )
    (net (code "7") (name "LED_BLUE") (class "Default")
      (node (ref "R3") (pin "2") (pinfunction "2_2") (pintype "passive"))
      (node (ref "U10") (pin "K2") (pinfunction "P0.05/AIN3_K2") (pintype "bidirectional"))
    )
    (net (code "8") (name "LED_GREEN") (class "Default")
      (node (ref "R2") (pin "2") (pinfunction "2_2") (pintype "passive"))
      (node (ref "U10") (pin "L1") (pinfunction "P0.06_L1") (pintype "bidirectional"))
    )
    (net (code "9") (name "LED_RED") (class "Default")
      (node (ref "R1") (pin "2") (pinfunction "2_2") (pintype "passive"))
      (node (ref "U10") (pin "J1") (pinfunction "P0.04/AIN2_J1") (pintype "bidirectional"))
    )
    (net (code "10") (name "MISO") (class "Default")
      (node (ref "TP4") (pin "P$1") (pinfunction "TESTPOINT_P$1") (pintype "bidirectional"))
      (node (ref "U1") (pin "6") (pinfunction "SDO_6") (pintype "bidirectional"))
      (node (ref "U10") (pin "R1") (pinfunction "P1.09_R1") (pintype "bidirectional"))
      (node (ref "U6") (pin "3") (pinfunction "MISO/SA0_3") (pintype "bidirectional"))
    )
    (net (code "11") (name "MOSI") (class "Default")
      (node (ref "TP5") (pin "P$1") (pinfunction "TESTPOINT_P$1") (pintype "bidirectional"))
      (node (ref "U1") (pin "9") (pinfunction "SDI_9") (pintype "bidirectional"))
      (node (ref "U10") (pin "N1") (pinfunction "P0.08_N1") (pintype "bidirectional"))
      (node (ref "U6") (pin "4") (pinfunction "MOSI/SDA_4") (pintype "bidirectional"))
    )
    (net (code "12") (name "Net-(A2-ANTENNA)") (class "Default")
      (node (ref "A2") (pin "S1") (pinfunction "ANTENNA_S1") (pintype "bidirectional"))
      (node (ref "C1") (pin "1") (pinfunction "1_1") (pintype "bidirectional"))
      (node (ref "L1") (pin "1") (pinfunction "1_1") (pintype "bidirectional"))
    )
    (net (code "13") (name "Net-(D2-B)") (class "Default")
      (node (ref "D2") (pin "3") (pinfunction "B_3") (pintype "output"))
      (node (ref "R3") (pin "1") (pinfunction "1_1") (pintype "passive"))
    )
    (net (code "14") (name "Net-(D2-G)") (class "Default")
      (node (ref "D2") (pin "4") (pinfunction "G_4") (pintype "output"))
      (node (ref "R2") (pin "1") (pinfunction "1_1") (pintype "passive"))
    )
    (net (code "15") (name "Net-(D2-R)") (class "Default")
      (node (ref "D2") (pin "2") (pinfunction "R_2") (pintype "output"))
      (node (ref "R1") (pin "1") (pinfunction "1_1") (pintype "passive"))
    )
    (net (code "16") (name "Net-(J5-D+)") (class "Default")
      (node (ref "J5") (pin "3") (pinfunction "D+_3") (pintype "bidirectional"))
      (node (ref "U4") (pin "14") (pinfunction "USBDP_14") (pintype "bidirectional"))
    )
    (net (code "17") (name "Net-(J5-D-)") (class "Default")
      (node (ref "J5") (pin "2") (pinfunction "D-_2") (pintype "bidirectional"))
      (node (ref "U4") (pin "15") (pinfunction "USBDM_15") (pintype "bidirectional"))
    )
    (net (code "18") (name "Net-(L2-Pad2)") (class "Default")
      (node (ref "L2") (pin "2") (pinfunction "2_2") (pintype "bidirectional"))
      (node (ref "L4") (pin "1") (pinfunction "1_1") (pintype "bidirectional"))
    )
    (net (code "19") (name "Net-(L5-1)") (class "Default")
      (node (ref "L5") (pin "P$1") (pinfunction "1_P$1") (pintype "bidirectional"))
      (node (ref "U2") (pin "20") (pinfunction "LBST_20") (pintype "bidirectional"))
    )
    (net (code "20") (name "Net-(Q1A-D)") (class "Default")
      (node (ref "Q1") (pin "6") (pinfunction "D_6") (pintype "passive"))
      (node (ref "U9") (pin "3") (pinfunction "SCL_3") (pintype "bidirectional"))
    )
    (net (code "21") (name "Net-(Q1B-D)") (class "Default")
      (node (ref "Q1") (pin "3") (pinfunction "D_3") (pintype "passive"))
      (node (ref "U9") (pin "2") (pinfunction "SDA_2") (pintype "bidirectional"))
    )
    (net (code "22") (name "Net-(Q2A-D)") (class "Default")
      (node (ref "Q2") (pin "6") (pinfunction "D_6") (pintype "passive"))
      (node (ref "U11") (pin "6") (pinfunction "SCL_6") (pintype "bidirectional"))
    )
    (net (code "23") (name "Net-(Q2B-D)") (class "Default")
      (node (ref "Q2") (pin "3") (pinfunction "D_3") (pintype "passive"))
      (node (ref "U11") (pin "1") (pinfunction "SDA_1") (pintype "bidirectional"))
    )
    (net (code "24") (name "Net-(Q3A-D)") (class "Default")
      (node (ref "Q3") (pin "6") (pinfunction "D_6") (pintype "passive"))
      (node (ref "U8") (pin "5") (pinfunction "SCL_5") (pintype "bidirectional"))
    )
    (net (code "25") (name "Net-(Q3B-D)") (class "Default")
      (node (ref "Q3") (pin "3") (pinfunction "D_3") (pintype "passive"))
      (node (ref "U8") (pin "6") (pinfunction "SDA_6") (pintype "bidirectional"))
    )
    (net (code "26") (name "Net-(Q4A-D)") (class "Default")
      (node (ref "Q4") (pin "6") (pinfunction "D_6") (pintype "passive"))
      (node (ref "U5") (pin "6") (pinfunction "SCL_6") (pintype "bidirectional"))
    )
    (net (code "27") (name "Net-(Q4B-D)") (class "Default")
      (node (ref "Q4") (pin "3") (pinfunction "D_3") (pintype "passive"))
      (node (ref "U5") (pin "4") (pinfunction "SDA_4") (pintype "bidirectional"))
    )
    (net (code "28") (name "Net-(Q5A-D)") (class "Default")
      (node (ref "C10") (pin "1") (pinfunction "1_1") (pintype "bidirectional"))
      (node (ref "C27") (pin "1") (pinfunction "1_1") (pintype "bidirectional"))
      (node (ref "Q5") (pin "6") (pinfunction "D_6") (pintype "passive"))
      (node (ref "U2") (pin "19") (pinfunction "VSTOR_19") (pintype "bidirectional"))
      (node (ref "U2") (pin "3") (pinfunction "VOC_SAMP_3") (pintype "bidirectional"))
    )
    (net (code "29") (name "Net-(Q5A-G)") (class "Default")
      (node (ref "Q5") (pin "2") (pinfunction "G_2") (pintype "passive"))
      (node (ref "Q5") (pin "5") (pinfunction "G_5") (pintype "passive"))
      (node (ref "U2") (pin "9") (pinfunction "~{VBAT_SEC_ON}_9") (pintype "bidirectional"))
    )
    (net (code "30") (name "Net-(Q5A-S)") (class "Default")
      (node (ref "Q5") (pin "1") (pinfunction "S_1") (pintype "passive"))
      (node (ref "Q5") (pin "4") (pinfunction "S_4") (pintype "passive"))
    )
    (net (code "31") (name "Net-(Q6A-G)") (class "Default")
      (node (ref "Q6") (pin "2") (pinfunction "G_2") (pintype "passive"))
      (node (ref "Q6") (pin "5") (pinfunction "G_5") (pintype "passive"))
      (node (ref "U2") (pin "10") (pinfunction "~{VBAT_PRI_ON}_10") (pintype "bidirectional"))
    )
    (net (code "32") (name "Net-(Q6A-S)") (class "Default")
      (node (ref "Q6") (pin "1") (pinfunction "S_1") (pintype "passive"))
      (node (ref "Q6") (pin "4") (pinfunction "S_4") (pintype "passive"))
    )
    (net (code "33") (name "Net-(Q7A-D)") (class "Default")
      (node (ref "Q7") (pin "6") (pinfunction "D_6") (pintype "passive"))
      (node (ref "U5") (pin "1") (pinfunction "VDD_1") (pintype "bidirectional"))
    )
    (net (code "34") (name "Net-(Q7B-D)") (class "Default")
      (node (ref "Q7") (pin "3") (pinfunction "D_3") (pintype "passive"))
      (node (ref "U8") (pin "1") (pinfunction "VCC_1") (pintype "bidirectional"))
    )
    (net (code "35") (name "Net-(Q8A-D)") (class "Default")
      (node (ref "Q8") (pin "6") (pinfunction "D_6") (pintype "passive"))
      (node (ref "U9") (pin "1") (pinfunction "VDD_1") (pintype "bidirectional"))
    )
    (net (code "36") (name "Net-(Q8B-D)") (class "Default")
      (node (ref "Q8") (pin "3") (pinfunction "D_3") (pintype "passive"))
      (node (ref "U11") (pin "5") (pinfunction "VCC_5") (pintype "bidirectional"))
    )
    (net (code "37") (name "Net-(Q10A-D)") (class "Default")
      (node (ref "Q10") (pin "6") (pinfunction "D_6") (pintype "passive"))
      (node (ref "U3") (pin "VCC") (pinfunction "VCC_VCC") (pintype "bidirectional"))
    )
    (net (code "38") (name "Net-(R14-Pad2)") (class "Default")
      (node (ref "R14") (pin "2") (pinfunction "2_2") (pintype "passive"))
      (node (ref "R4") (pin "2") (pinfunction "2_2") (pintype "passive"))
      (node (ref "SJ1") (pin "3") (pinfunction "3_3") (pintype "passive"))
    )
    (net (code "39") (name "Net-(R19-Pad2)") (class "Default")
      (node (ref "R19") (pin "2") (pinfunction "2_2") (pintype "passive"))
      (node (ref "R5") (pin "2") (pinfunction "2_2") (pintype "passive"))
      (node (ref "SJ1") (pin "1") (pinfunction "1_1") (pintype "passive"))
    )
    (net (code "40") (name "Net-(U1-AF)") (class "Default")
      (node (ref "C7") (pin "1") (pinfunction "1_1") (pintype "bidirectional"))
      (node (ref "U1") (pin "14") (pinfunction "AF_14") (pintype "bidirectional"))
    )
    (net (code "41") (name "Net-(U1-XI)") (class "Default")
      (node (ref "C32") (pin "1") (pinfunction "1_1") (pintype "bidirectional"))
      (node (ref "U1") (pin "16") (pinfunction "XI_16") (pintype "bidirectional"))
      (node (ref "X4") (pin "1") (pinfunction "1_1") (pintype "bidirectional"))
    )
    (net (code "42") (name "Net-(U1-XO)") (class "Default")
      (node (ref "C33") (pin "1") (pinfunction "1_1") (pintype "bidirectional"))
      (node (ref "U1") (pin "15") (pinfunction "XO_15") (pintype "bidirectional"))
      (node (ref "X4") (pin "2") (pinfunction "2_2") (pintype "bidirectional"))
    )
    (net (code "43") (name "Net-(U1-~{EXTR})") (class "Default")
      (node (ref "R10") (pin "1") (pinfunction "1_1") (pintype "passive"))
      (node (ref "S1") (pin "P$2") (pinfunction "P$2_P$2") (pintype "passive"))
      (node (ref "S1") (pin "P$4") (pinfunction "P$2_P$4") (pintype "passive"))
      (node (ref "U1") (pin "3") (pinfunction "~{EXTR}_3") (pintype "bidirectional"))
    )
    (net (code "44") (name "Net-(U2-OK_HYST)") (class "Default")
      (node (ref "R17") (pin "2") (pinfunction "2_2") (pintype "passive"))
      (node (ref "R20") (pin "2") (pinfunction "2_2") (pintype "passive"))
      (node (ref "R4") (pin "1") (pinfunction "1_1") (pintype "passive"))
      (node (ref "R5") (pin "1") (pinfunction "1_1") (pintype "passive"))
      (node (ref "U2") (pin "11") (pinfunction "OK_HYST_11") (pintype "bidirectional"))
    )
    (net (code "45") (name "Net-(U2-OK_PROG)") (class "Default")
      (node (ref "R15") (pin "2") (pinfunction "2_2") (pintype "passive"))
      (node (ref "R17") (pin "1") (pinfunction "1_1") (pintype "passive"))
      (node (ref "R18") (pin "2") (pinfunction "2_2") (pintype "passive"))
      (node (ref "R20") (pin "1") (pinfunction "1_1") (pintype "passive"))
      (node (ref "U2") (pin "12") (pinfunction "OK_PROG_12") (pintype "bidirectional"))
    )
    (net (code "46") (name "Net-(U2-VBAT_OV)") (class "Default")
      (node (ref "R14") (pin "1") (pinfunction "1_1") (pintype "passive"))
      (node (ref "R16") (pin "2") (pinfunction "2_2") (pintype "passive"))
      (node (ref "R19") (pin "1") (pinfunction "1_1") (pintype "passive"))
      (node (ref "R21") (pin "2") (pinfunction "2_2") (pintype "passive"))
      (node (ref "U2") (pin "7") (pinfunction "VBAT_OV_7") (pintype "bidirectional"))
    )
    (net (code "47") (name "Net-(U2-VRDIV)") (class "Default")
      (node (ref "SJ1") (pin "2") (pinfunction "2_2") (pintype "passive"))
      (node (ref "U2") (pin "8") (pinfunction "VRDIV_8") (pintype "bidirectional"))
    )
    (net (code "48") (name "Net-(U2-VREF_SAMP)") (class "Default")
      (node (ref "C9") (pin "1") (pinfunction "1_1") (pintype "bidirectional"))
      (node (ref "U2") (pin "4") (pinfunction "VREF_SAMP_4") (pintype "bidirectional"))
    )
    (net (code "49") (name "Net-(U4-3V3OUT)") (class "Default")
      (node (ref "C20") (pin "1") (pinfunction "1_1") (pintype "bidirectional"))
      (node (ref "U4") (pin "16") (pinfunction "3V3OUT_16") (pintype "output"))
    )
    (net (code "50") (name "Net-(U4-RXD)") (class "Default")
      (node (ref "SJ4") (pin "1") (pinfunction "1_1") (pintype "passive"))
      (node (ref "U4") (pin "2") (pinfunction "RXD_2") (pintype "input"))
    )
    (net (code "51") (name "Net-(U4-TXD)") (class "Default")
      (node (ref "SJ5") (pin "1") (pinfunction "1_1") (pintype "passive"))
      (node (ref "U4") (pin "30") (pinfunction "TXD_30") (pintype "output"))
    )
    (net (code "52") (name "Net-(U4-VCCIO)") (class "Default")
      (node (ref "SJ2") (pin "2") (pinfunction "2_2") (pintype "passive"))
      (node (ref "U4") (pin "1") (pinfunction "VCCIO_1") (pintype "power_in"))
    )
    (net (code "53") (name "Net-(U4-~{RESET})") (class "Default")
      (node (ref "SJ3") (pin "2") (pinfunction "2_2") (pintype "passive"))
      (node (ref "U4") (pin "18") (pinfunction "~{RESET}_18") (pintype "input"))
    )
    (net (code "54") (name "Net-(U7-EN)") (class "Default")
      (node (ref "R22") (pin "1") (pinfunction "1_1") (pintype "passive"))
      (node (ref "U7") (pin "6") (pinfunction "EN_6") (pintype "bidirectional"))
    )
    (net (code "55") (name "Net-(U7-SEL)") (class "Default")
      (node (ref "R13") (pin "2") (pinfunction "2_2") (pintype "passive"))
      (node (ref "U7") (pin "4") (pinfunction "SEL_4") (pintype "bidirectional"))
    )
    (net (code "56") (name "Net-(U10-ANT)") (class "Default")
      (node (ref "C2") (pin "1") (pinfunction "1_1") (pintype "bidirectional"))
      (node (ref "L1") (pin "2") (pinfunction "2_2") (pintype "bidirectional"))
      (node (ref "U10") (pin "H23") (pinfunction "ANT_H23") (pintype "bidirectional"))
    )
    (net (code "57") (name "Net-(U10-DCC)") (class "Default")
      (node (ref "L4") (pin "2") (pinfunction "2_2") (pintype "bidirectional"))
      (node (ref "U10") (pin "B3") (pinfunction "DCC_B3") (pintype "bidirectional"))
    )
    (net (code "58") (name "Net-(U10-DEC1)") (class "Default")
      (node (ref "C14") (pin "1") (pinfunction "1_1") (pintype "bidirectional"))
      (node (ref "U10") (pin "C1") (pinfunction "DEC1_C1") (pintype "bidirectional"))
    )
    (net (code "59") (name "Net-(U10-DEC3)") (class "Default")
      (node (ref "C8") (pin "1") (pinfunction "1_1") (pintype "bidirectional"))
      (node (ref "U10") (pin "D23") (pinfunction "DEC3_D23") (pintype "bidirectional"))
    )
    (net (code "60") (name "Net-(U10-DEC4)") (class "Default")
      (node (ref "C11") (pin "1") (pinfunction "1_1") (pintype "bidirectional"))
      (node (ref "C22") (pin "1") (pinfunction "1_1") (pintype "bidirectional"))
      (node (ref "L2") (pin "1") (pinfunction "1_1") (pintype "bidirectional"))
      (node (ref "U10") (pin "B5") (pinfunction "DEC4_B5") (pintype "bidirectional"))
      (node (ref "U10") (pin "E24") (pinfunction "DEC6_E24") (pintype "bidirectional"))
    )
    (net (code "61") (name "Net-(U10-P0.00{slash}XL1)") (class "Default")
      (node (ref "C6") (pin "2") (pinfunction "2_2") (pintype "bidirectional"))
      (node (ref "U10") (pin "D2") (pinfunction "P0.00/XL1_D2") (pintype "bidirectional"))
      (node (ref "X3") (pin "A") (pinfunction "1_A") (pintype "bidirectional"))
    )
    (net (code "62") (name "Net-(U10-P0.01{slash}XL2)") (class "Default")
      (node (ref "C5") (pin "2") (pinfunction "2_2") (pintype "bidirectional"))
      (node (ref "U10") (pin "F2") (pinfunction "P0.01/XL2_F2") (pintype "bidirectional"))
      (node (ref "X3") (pin "B") (pinfunction "2_B") (pintype "bidirectional"))
    )
    (net (code "63") (name "Net-(U10-XC1)") (class "Default")
      (node (ref "C3") (pin "2") (pinfunction "2_2") (pintype "bidirectional"))
      (node (ref "U10") (pin "B24") (pinfunction "XC1_B24") (pintype "bidirectional"))
      (node (ref "X1") (pin "3") (pinfunction "2_3") (pintype "bidirectional"))
    )
    (net (code "64") (name "Net-(U10-XC2)") (class "Default")
      (node (ref "C4") (pin "2") (pinfunction "2_2") (pintype "bidirectional"))
      (node (ref "U10") (pin "A23") (pinfunction "XC2_A23") (pintype "bidirectional"))
      (node (ref "X1") (pin "1") (pinfunction "1_1") (pintype "bidirectional"))
    )
    (net (code "65") (name "PIR_OUT") (class "Default")
      (node (ref "TP22") (pin "P$1") (pinfunction "TESTPOINT_P$1") (pintype "bidirectional"))
      (node (ref "U10") (pin "AC11") (pinfunction "P0.16_AC11") (pintype "bidirectional"))
      (node (ref "U3") (pin "OUT") (pinfunction "OUT_OUT") (pintype "bidirectional"))
    )
    (net (code "66") (name "RTC_CS") (class "Default")
      (node (ref "TP6") (pin "P$1") (pinfunction "TESTPOINT_P$1") (pintype "bidirectional"))
      (node (ref "U1") (pin "12") (pinfunction "~{CS}_12") (pintype "bidirectional"))
      (node (ref "U10") (pin "B17") (pinfunction "P1.12_B17") (pintype "bidirectional"))
    )
    (net (code "67") (name "SCK") (class "Default")
      (node (ref "TP3") (pin "P$1") (pinfunction "TESTPOINT_P$1") (pintype "bidirectional"))
      (node (ref "U1") (pin "7") (pinfunction "SCL_7") (pintype "bidirectional"))
      (node (ref "U10") (pin "U1") (pinfunction "P0.12_U1") (pintype "bidirectional"))
      (node (ref "U6") (pin "1") (pinfunction "SCL/SPC_1") (pintype "bidirectional"))
    )
    (net (code "68") (name "SCL") (class "Default")
      (node (ref "Q1") (pin "1") (pinfunction "S_1") (pintype "passive"))
      (node (ref "Q2") (pin "1") (pinfunction "S_1") (pintype "passive"))
      (node (ref "Q3") (pin "1") (pinfunction "S_1") (pintype "passive"))
      (node (ref "Q4") (pin "1") (pinfunction "S_1") (pintype "passive"))
      (node (ref "R6") (pin "1") (pinfunction "1_1") (pintype "passive"))
      (node (ref "TP2") (pin "P$1") (pinfunction "TESTPOINT_P$1") (pintype "bidirectional"))
      (node (ref "U10") (pin "AC9") (pinfunction "P0.14_AC9") (pintype "bidirectional"))
    )
    (net (code "69") (name "SDA") (class "Default")
      (node (ref "Q1") (pin "4") (pinfunction "S_4") (pintype "passive"))
      (node (ref "Q2") (pin "4") (pinfunction "S_4") (pintype "passive"))
      (node (ref "Q3") (pin "4") (pinfunction "S_4") (pintype "passive"))
      (node (ref "Q4") (pin "4") (pinfunction "S_4") (pintype "passive"))
      (node (ref "R7") (pin "1") (pinfunction "1_1") (pintype "passive"))
      (node (ref "TP1") (pin "P$1") (pinfunction "TESTPOINT_P$1") (pintype "bidirectional"))
      (node (ref "U10") (pin "AD10") (pinfunction "P0.15_AD10") (pintype "bidirectional"))
    )
    (net (code "70") (name "SW") (class "Default")
      (node (ref "L3") (pin "P$2") (pinfunction "2_P$2") (pintype "bidirectional"))
      (node (ref "TP25") (pin "P$1") (pinfunction "TESTPOINT_P$1") (pintype "bidirectional"))
      (node (ref "U10") (pin "B11") (pinfunction "P0.28/AIN4_B11") (pintype "bidirectional"))
      (node (ref "U7") (pin "2") (pinfunction "LX_2") (pintype "bidirectional"))
    )
    (net (code "71") (name "SWDCLK") (class "Default")
      (node (ref "J1") (pin "4") (pinfunction "SWDCLK_4") (pintype "bidirectional"))
      (node (ref "U10") (pin "AA24") (pinfunction "SWDCLK_AA24") (pintype "bidirectional"))
    )
    (net (code "72") (name "SWDIO") (class "Default")
      (node (ref "J1") (pin "2") (pinfunction "SWDIO_2") (pintype "bidirectional"))
      (node (ref "U10") (pin "AC24") (pinfunction "SWDIO_AC24") (pintype "bidirectional"))
    )
    (net (code "73") (name "USB_5V") (class "Default")
      (node (ref "J5") (pin "1") (pinfunction "+5V_1") (pintype "bidirectional"))
      (node (ref "U4") (pin "19") (pinfunction "VCC_19") (pintype "power_in"))
    )
    (net (code "74") (name "VBAT") (class "Default")
      (node (ref "BT2") (pin "POS1") (pinfunction "+_POS1") (pintype "bidirectional"))
      (node (ref "BT2") (pin "POS2") (pinfunction "+_POS2") (pintype "bidirectional"))
      (node (ref "BT2") (pin "POS3") (pinfunction "+_POS3") (pintype "bidirectional"))
      (node (ref "BT2") (pin "POS4") (pinfunction "+_POS4") (pintype "bidirectional"))
      (node (ref "BT3") (pin "POS1") (pinfunction "+_POS1") (pintype "bidirectional"))
      (node (ref "BT3") (pin "POS2") (pinfunction "+_POS2") (pintype "bidirectional"))
      (node (ref "BT3") (pin "POS3") (pinfunction "+_POS3") (pintype "bidirectional"))
      (node (ref "BT3") (pin "POS4") (pinfunction "+_POS4") (pintype "bidirectional"))
      (node (ref "BT4") (pin "+") (pinfunction "+_+") (pintype "bidirectional"))
      (node (ref "Q6") (pin "6") (pinfunction "D_6") (pintype "passive"))
      (node (ref "U1") (pin "5") (pinfunction "VBAT_5") (pintype "bidirectional"))
      (node (ref "U10") (pin "A10") (pinfunction "P0.29/AIN5_A10") (pintype "bidirectional"))
      (node (ref "U2") (pin "14") (pinfunction "VBAT_PRI_14") (pintype "bidirectional"))
    )
    (net (code "75") (name "VCC") (class "Default")
      (node (ref "C12") (pin "1") (pinfunction "1_1") (pintype "bidirectional"))
      (node (ref "C13") (pin "1") (pinfunction "1_1") (pintype "bidirectional"))
      (node (ref "C15") (pin "1") (pinfunction "1_1") (pintype "bidirectional"))
      (node (ref "C16") (pin "1") (pinfunction "1_1") (pintype "bidirectional"))
      (node (ref "C17") (pin "1") (pinfunction "1_1") (pintype "bidirectional"))
      (node (ref "C18") (pin "1") (pinfunction "1_1") (pintype "bidirectional"))
      (node (ref "C19") (pin "1") (pinfunction "1_1") (pintype "bidirectional"))
      (node (ref "C21") (pin "1") (pinfunction "1_1") (pintype "bidirectional"))
      (node (ref "C23") (pin "1") (pinfunction "1_1") (pintype "bidirectional"))
      (node (ref "C24") (pin "1") (pinfunction "1_1") (pintype "bidirectional"))
      (node (ref "C25") (pin "1") (pinfunction "1_1") (pintype "bidirectional"))
      (node (ref "C26") (pin "1") (pinfunction "1_1") (pintype "bidirectional"))
      (node (ref "C30") (pin "1") (pinfunction "1_1") (pintype "bidirectional"))
      (node (ref "C31") (pin "1") (pinfunction "1_1") (pintype "bidirectional"))
      (node (ref "D2") (pin "1") (pinfunction "VDD_1") (pintype "bidirectional"))
      (node (ref "J1") (pin "1") (pinfunction "VCC_1") (pintype "bidirectional"))
      (node (ref "Q10") (pin "1") (pinfunction "S_1") (pintype "passive"))
      (node (ref "Q7") (pin "1") (pinfunction "S_1") (pintype "passive"))
      (node (ref "Q7") (pin "4") (pinfunction "S_4") (pintype "passive"))
      (node (ref "Q8") (pin "1") (pinfunction "S_1") (pintype "passive"))
      (node (ref "Q8") (pin "4") (pinfunction "S_4") (pintype "passive"))
      (node (ref "R10") (pin "2") (pinfunction "2_2") (pintype "passive"))
      (node (ref "R11") (pin "2") (pinfunction "2_2") (pintype "passive"))
      (node (ref "R12") (pin "2") (pinfunction "2_2") (pintype "passive"))
      (node (ref "R23") (pin "2") (pinfunction "2_2") (pintype "passive"))
      (node (ref "R24") (pin "2") (pinfunction "2_2") (pintype "passive"))
      (node (ref "R25") (pin "2") (pinfunction "2_2") (pintype "passive"))
      (node (ref "R26") (pin "2") (pinfunction "2_2") (pintype "passive"))
      (node (ref "R27") (pin "2") (pinfunction "2_2") (pintype "passive"))
      (node (ref "R6") (pin "2") (pinfunction "2_2") (pintype "passive"))
      (node (ref "R7") (pin "2") (pinfunction "2_2") (pintype "passive"))
      (node (ref "R8") (pin "2") (pinfunction "2_2") (pintype "passive"))
      (node (ref "R9") (pin "2") (pinfunction "2_2") (pintype "passive"))
      (node (ref "SJ2") (pin "1") (pinfunction "1_1") (pintype "passive"))
      (node (ref "TP26") (pin "P$1") (pinfunction "TESTPOINT_P$1") (pintype "bidirectional"))
      (node (ref "U1") (pin "13") (pinfunction "VCC_13") (pintype "bidirectional"))
      (node (ref "U10") (pin "A22") (pinfunction "VDD_A22") (pintype "bidirectional"))
      (node (ref "U10") (pin "AD14") (pinfunction "VDD_AD14") (pintype "bidirectional"))
      (node (ref "U10") (pin "AD23") (pinfunction "VDD_AD23") (pintype "bidirectional"))
      (node (ref "U10") (pin "B1") (pinfunction "VDD_B1") (pintype "bidirectional"))
      (node (ref "U10") (pin "W1") (pinfunction "VDD_W1") (pintype "bidirectional"))
      (node (ref "U10") (pin "Y2") (pinfunction "VDDH_Y2") (pintype "bidirectional"))
      (node (ref "U6") (pin "10") (pinfunction "VDD_IO_10") (pintype "bidirectional"))
      (node (ref "U6") (pin "9") (pinfunction "VCC_9") (pintype "bidirectional"))
      (node (ref "U7") (pin "1") (pinfunction "OUT_1") (pintype "bidirectional"))
    )
    (net (code "76") (name "VSEC") (class "Default")
      (node (ref "BT1") (pin "+") (pinfunction "+_+") (pintype "bidirectional"))
      (node (ref "TP24") (pin "P$1") (pinfunction "TESTPOINT_P$1") (pintype "bidirectional"))
      (node (ref "U10") (pin "A8") (pinfunction "P0.31/AIN7_A8") (pintype "bidirectional"))
      (node (ref "U2") (pin "18") (pinfunction "VBAT_SEC_18") (pintype "bidirectional"))
    )
    (net (code "77") (name "VSOL") (class "Default")
      (node (ref "C28") (pin "1") (pinfunction "1_1") (pintype "bidirectional"))
      (node (ref "D1") (pin "+") (pinfunction "V+_+") (pintype "bidirectional"))
      (node (ref "L5") (pin "P$2") (pinfunction "2_P$2") (pintype "bidirectional"))
      (node (ref "TP23") (pin "P$1") (pinfunction "TESTPOINT_P$1") (pintype "bidirectional"))
      (node (ref "U10") (pin "B9") (pinfunction "P0.30/AIN6_B9") (pintype "bidirectional"))
      (node (ref "U2") (pin "2") (pinfunction "VIN_DC_2") (pintype "bidirectional"))
    )
    (net (code "78") (name "VSW") (class "Default")
      (node (ref "C29") (pin "1") (pinfunction "1_1") (pintype "bidirectional"))
      (node (ref "L3") (pin "P$1") (pinfunction "1_P$1") (pintype "bidirectional"))
      (node (ref "Q5") (pin "3") (pinfunction "D_3") (pintype "passive"))
      (node (ref "Q6") (pin "3") (pinfunction "D_3") (pintype "passive"))
      (node (ref "R22") (pin "2") (pinfunction "2_2") (pintype "passive"))
      (node (ref "U7") (pin "5") (pinfunction "IN_5") (pintype "bidirectional"))
    )
    (net (code "79") (name "WDI") (class "Default")
      (node (ref "R12") (pin "1") (pinfunction "1_1") (pintype "passive"))
      (node (ref "TP16") (pin "P$1") (pinfunction "TESTPOINT_P$1") (pintype "bidirectional"))
      (node (ref "U1") (pin "2") (pinfunction "WDI_2") (pintype "bidirectional"))
      (node (ref "U10") (pin "A12") (pinfunction "P0.02/AIN0_A12") (pintype "bidirectional"))
    )
    (net (code "80") (name "unconnected-(J1-SWO-Pad6)") (class "Default")
      (node (ref "J1") (pin "6") (pinfunction "SWO_6") (pintype "bidirectional"))
    )
    (net (code "81") (name "unconnected-(J5-ID-Pad4)") (class "Default")
      (node (ref "J5") (pin "4") (pinfunction "ID_4") (pintype "bidirectional"))
    )
    (net (code "82") (name "unconnected-(U1-EXTI-Pad10)") (class "Default")
      (node (ref "U1") (pin "10") (pinfunction "EXTI_10") (pintype "bidirectional"))
    )
    (net (code "83") (name "unconnected-(U2-VBAT_OK-Pad13)") (class "Default")
      (node (ref "U2") (pin "13") (pinfunction "VBAT_OK_13") (pintype "bidirectional"))
    )
    (net (code "84") (name "unconnected-(U2-~{EN}-Pad5)") (class "Default")
      (node (ref "U2") (pin "5") (pinfunction "~{EN}_5") (pintype "bidirectional"))
    )
    (net (code "85") (name "unconnected-(U4-CBUS0-Pad22)") (class "Default")
      (node (ref "U4") (pin "22") (pinfunction "CBUS0_22") (pintype "bidirectional"))
    )
    (net (code "86") (name "unconnected-(U4-CBUS1-Pad21)") (class "Default")
      (node (ref "U4") (pin "21") (pinfunction "CBUS1_21") (pintype "bidirectional"))
    )
    (net (code "87") (name "unconnected-(U4-CBUS2-Pad10)") (class "Default")
      (node (ref "U4") (pin "10") (pinfunction "CBUS2_10") (pintype "bidirectional"))
    )
    (net (code "88") (name "unconnected-(U4-CBUS3-Pad11)") (class "Default")
      (node (ref "U4") (pin "11") (pinfunction "CBUS3_11") (pintype "bidirectional"))
    )
    (net (code "89") (name "unconnected-(U4-CBUS4-Pad9)") (class "Default")
      (node (ref "U4") (pin "9") (pinfunction "CBUS4_9") (pintype "bidirectional"))
    )
    (net (code "90") (name "unconnected-(U4-OSCI-Pad27)") (class "Default")
      (node (ref "U4") (pin "27") (pinfunction "OSCI_27") (pintype "input"))
    )
    (net (code "91") (name "unconnected-(U4-OSCO-Pad28)") (class "Default")
      (node (ref "U4") (pin "28") (pinfunction "OSCO_28") (pintype "output"))
    )
    (net (code "92") (name "unconnected-(U4-~{CTS}-Pad8)") (class "Default")
      (node (ref "U4") (pin "8") (pinfunction "~{CTS}_8") (pintype "input"))
    )
    (net (code "93") (name "unconnected-(U4-~{DCD}-Pad7)") (class "Default")
      (node (ref "U4") (pin "7") (pinfunction "~{DCD}_7") (pintype "input"))
    )
    (net (code "94") (name "unconnected-(U4-~{DSR}-Pad6)") (class "Default")
      (node (ref "U4") (pin "6") (pinfunction "~{DSR}_6") (pintype "input"))
    )
    (net (code "95") (name "unconnected-(U4-~{DTR}-Pad31)") (class "Default")
      (node (ref "U4") (pin "31") (pinfunction "~{DTR}_31") (pintype "output"))
    )
    (net (code "96") (name "unconnected-(U4-~{RI}-Pad3)") (class "Default")
      (node (ref "U4") (pin "3") (pinfunction "~{RI}_3") (pintype "input"))
    )
    (net (code "97") (name "unconnected-(U4-~{RTS}-Pad32)") (class "Default")
      (node (ref "U4") (pin "32") (pinfunction "~{RTS}_32") (pintype "output"))
    )
    (net (code "98") (name "unconnected-(U10-D+-PadAD6)") (class "Default")
      (node (ref "U10") (pin "AD6") (pinfunction "D+_AD6") (pintype "bidirectional"))
    )
    (net (code "99") (name "unconnected-(U10-D--PadAD4)") (class "Default")
      (node (ref "U10") (pin "AD4") (pinfunction "D-_AD4") (pintype "bidirectional"))
    )
    (net (code "100") (name "unconnected-(U10-DCCH-PadAB2)") (class "Default")
      (node (ref "U10") (pin "AB2") (pinfunction "DCCH_AB2") (pintype "bidirectional"))
    )
    (net (code "101") (name "unconnected-(U10-DEC2-PadA18)") (class "Default")
      (node (ref "U10") (pin "A18") (pinfunction "DEC2_A18") (pintype "bidirectional"))
    )
    (net (code "102") (name "unconnected-(U10-DEC5-PadN24)") (class "Default")
      (node (ref "U10") (pin "N24") (pinfunction "DEC5_N24") (pintype "bidirectional"))
    )
    (net (code "103") (name "unconnected-(U10-DECUSB-PadAC5)") (class "Default")
      (node (ref "U10") (pin "AC5") (pinfunction "DECUSB_AC5") (pintype "bidirectional"))
    )
    (net (code "104") (name "unconnected-(U10-P0.03{slash}AIN1-PadB13)") (class "Default")
      (node (ref "U10") (pin "B13") (pinfunction "P0.03/AIN1_B13") (pintype "bidirectional"))
    )
    (net (code "105") (name "unconnected-(U10-P0.07-PadM2)") (class "Default")
      (node (ref "U10") (pin "M2") (pinfunction "P0.07_M2") (pintype "bidirectional"))
    )
    (net (code "106") (name "unconnected-(U10-P0.09{slash}NFC1-PadL24)") (class "Default")
      (node (ref "U10") (pin "L24") (pinfunction "P0.09/NFC1_L24") (pintype "bidirectional"))
    )
    (net (code "107") (name "unconnected-(U10-P0.10{slash}NFC2-PadJ24)") (class "Default")
      (node (ref "U10") (pin "J24") (pinfunction "P0.10/NFC2_J24") (pintype "bidirectional"))
    )
    (net (code "108") (name "unconnected-(U10-P0.11-PadT2)") (class "Default")
      (node (ref "U10") (pin "T2") (pinfunction "P0.11_T2") (pintype "bidirectional"))
    )
    (net (code "109") (name "unconnected-(U10-P0.13-PadAD8)") (class "Default")
      (node (ref "U10") (pin "AD8") (pinfunction "P0.13_AD8") (pintype "bidirectional"))
    )
    (net (code "110") (name "unconnected-(U10-P0.19-PadAC15)") (class "Default")
      (node (ref "U10") (pin "AC15") (pinfunction "P0.19_AC15") (pintype "bidirectional"))
    )
    (net (code "111") (name "unconnected-(U10-P1.01-PadY23)") (class "Default")
      (node (ref "U10") (pin "Y23") (pinfunction "P1.01_Y23") (pintype "bidirectional"))
    )
    (net (code "112") (name "unconnected-(U10-P1.02-PadW24)") (class "Default")
      (node (ref "U10") (pin "W24") (pinfunction "P1.02_W24") (pintype "bidirectional"))
    )
    (net (code "113") (name "unconnected-(U10-P1.03-PadV23)") (class "Default")
      (node (ref "U10") (pin "V23") (pinfunction "P1.03_V23") (pintype "bidirectional"))
    )
    (net (code "114") (name "unconnected-(U10-P1.04-PadU24)") (class "Default")
      (node (ref "U10") (pin "U24") (pinfunction "P1.04_U24") (pintype "bidirectional"))
    )
    (net (code "115") (name "unconnected-(U10-P1.05-PadT23)") (class "Default")
      (node (ref "U10") (pin "T23") (pinfunction "P1.05_T23") (pintype "bidirectional"))
    )
    (net (code "116") (name "unconnected-(U10-P1.06-PadR24)") (class "Default")
      (node (ref "U10") (pin "R24") (pinfunction "P1.06_R24") (pintype "bidirectional"))
    )
    (net (code "117") (name "unconnected-(U10-P1.07-PadP23)") (class "Default")
      (node (ref "U10") (pin "P23") (pinfunction "P1.07_P23") (pintype "bidirectional"))
    )
    (net (code "118") (name "unconnected-(U10-P1.08-PadP2)") (class "Default")
      (node (ref "U10") (pin "P2") (pinfunction "P1.08_P2") (pintype "bidirectional"))
    )
    (net (code "119") (name "~{CLR_EN}") (class "Default")
      (node (ref "Q4") (pin "2") (pinfunction "G_2") (pintype "passive"))
      (node (ref "Q4") (pin "5") (pinfunction "G_5") (pintype "passive"))
      (node (ref "Q7") (pin "2") (pinfunction "G_2") (pintype "passive"))
      (node (ref "R23") (pin "1") (pinfunction "1_1") (pintype "passive"))
      (node (ref "TP9") (pin "P$1") (pinfunction "TESTPOINT_P$1") (pintype "bidirectional"))
      (node (ref "U10") (pin "AC21") (pinfunction "P0.25_AC21") (pintype "bidirectional"))
    )
    (net (code "120") (name "~{CLR_INT}") (class "Default")
      (node (ref "R8") (pin "1") (pinfunction "1_1") (pintype "passive"))
      (node (ref "TP20") (pin "P$1") (pinfunction "TESTPOINT_P$1") (pintype "bidirectional"))
      (node (ref "U10") (pin "AC19") (pinfunction "P0.23_AC19") (pintype "bidirectional"))
      (node (ref "U5") (pin "5") (pinfunction "~{INT}_5") (pintype "bidirectional"))
    )
    (net (code "121") (name "~{HUM_EN}") (class "Default")
      (node (ref "Q2") (pin "2") (pinfunction "G_2") (pintype "passive"))
      (node (ref "Q2") (pin "5") (pinfunction "G_5") (pintype "passive"))
      (node (ref "Q8") (pin "5") (pinfunction "G_5") (pintype "passive"))
      (node (ref "R26") (pin "1") (pinfunction "1_1") (pintype "passive"))
      (node (ref "TP12") (pin "P$1") (pinfunction "TESTPOINT_P$1") (pintype "bidirectional"))
      (node (ref "U10") (pin "A20") (pinfunction "P1.10_A20") (pintype "bidirectional"))
    )
    (net (code "122") (name "~{LT_EN}") (class "Default")
      (node (ref "Q3") (pin "2") (pinfunction "G_2") (pintype "passive"))
      (node (ref "Q3") (pin "5") (pinfunction "G_5") (pintype "passive"))
      (node (ref "Q7") (pin "5") (pinfunction "G_5") (pintype "passive"))
      (node (ref "R24") (pin "1") (pinfunction "1_1") (pintype "passive"))
      (node (ref "TP10") (pin "P$1") (pinfunction "TESTPOINT_P$1") (pintype "bidirectional"))
      (node (ref "U10") (pin "AD20") (pinfunction "P0.24_AD20") (pintype "bidirectional"))
    )
    (net (code "123") (name "~{LT_INT}") (class "Default")
      (node (ref "R9") (pin "1") (pinfunction "1_1") (pintype "passive"))
      (node (ref "TP21") (pin "P$1") (pinfunction "TESTPOINT_P$1") (pintype "bidirectional"))
      (node (ref "U10") (pin "AD22") (pinfunction "P1.00_AD22") (pintype "bidirectional"))
      (node (ref "U8") (pin "4") (pinfunction "~{INT}_4") (pintype "bidirectional"))
    )
    (net (code "124") (name "~{PIR_EN}") (class "Default")
      (node (ref "Q10") (pin "2") (pinfunction "G_2") (pintype "passive"))
      (node (ref "R27") (pin "1") (pinfunction "1_1") (pintype "passive"))
      (node (ref "TP11") (pin "P$1") (pinfunction "TESTPOINT_P$1") (pintype "bidirectional"))
      (node (ref "U10") (pin "AD12") (pinfunction "P0.17_AD12") (pintype "bidirectional"))
    )
    (net (code "125") (name "~{PR_EN}") (class "Default")
      (node (ref "Q1") (pin "2") (pinfunction "G_2") (pintype "passive"))
      (node (ref "Q1") (pin "5") (pinfunction "G_5") (pintype "passive"))
      (node (ref "Q8") (pin "2") (pinfunction "G_2") (pintype "passive"))
      (node (ref "R25") (pin "1") (pinfunction "1_1") (pintype "passive"))
      (node (ref "TP8") (pin "P$1") (pinfunction "TESTPOINT_P$1") (pintype "bidirectional"))
      (node (ref "U10") (pin "B19") (pinfunction "P1.11_B19") (pintype "bidirectional"))
    )
    (net (code "126") (name "~{RST}") (class "Default")
      (node (ref "J1") (pin "3") (pinfunction "~{RESET}_3") (pintype "bidirectional"))
      (node (ref "R11") (pin "1") (pinfunction "1_1") (pintype "passive"))
      (node (ref "SJ3") (pin "1") (pinfunction "1_1") (pintype "passive"))
      (node (ref "TP17") (pin "P$1") (pinfunction "TESTPOINT_P$1") (pintype "bidirectional"))
      (node (ref "U1") (pin "1") (pinfunction "~{RST}_1") (pintype "bidirectional"))
      (node (ref "U10") (pin "AC13") (pinfunction "P0.18_AC13") (pintype "bidirectional"))
    )
    (net (code "127") (name "~{RTC_IRQ1}") (class "Default")
      (node (ref "TP13") (pin "P$1") (pinfunction "TESTPOINT_P$1") (pintype "bidirectional"))
      (node (ref "U1") (pin "11") (pinfunction "FOUT/~{IRQ1}_11") (pintype "bidirectional"))
      (node (ref "U10") (pin "A16") (pinfunction "P1.13_A16") (pintype "bidirectional"))
    )
    (net (code "128") (name "~{RTC_IRQ2}") (class "Default")
      (node (ref "TP14") (pin "P$1") (pinfunction "TESTPOINT_P$1") (pintype "bidirectional"))
      (node (ref "U1") (pin "4") (pinfunction "~{IRQ2}_4") (pintype "bidirectional"))
      (node (ref "U10") (pin "B15") (pinfunction "P1.14_B15") (pintype "bidirectional"))
    )
    (net (code "129") (name "~{RTC_IRQ3}") (class "Default")
      (node (ref "TP15") (pin "P$1") (pinfunction "TESTPOINT_P$1") (pintype "bidirectional"))
      (node (ref "U1") (pin "8") (pinfunction "CLKOUT/~{IRQ3}_8") (pintype "bidirectional"))
      (node (ref "U10") (pin "A14") (pinfunction "P1.15_A14") (pintype "bidirectional"))
    )
  )
)
